# Clocks_Freq_Synth_board.net
KiCad netlist of a schematic drawn in EAGLE
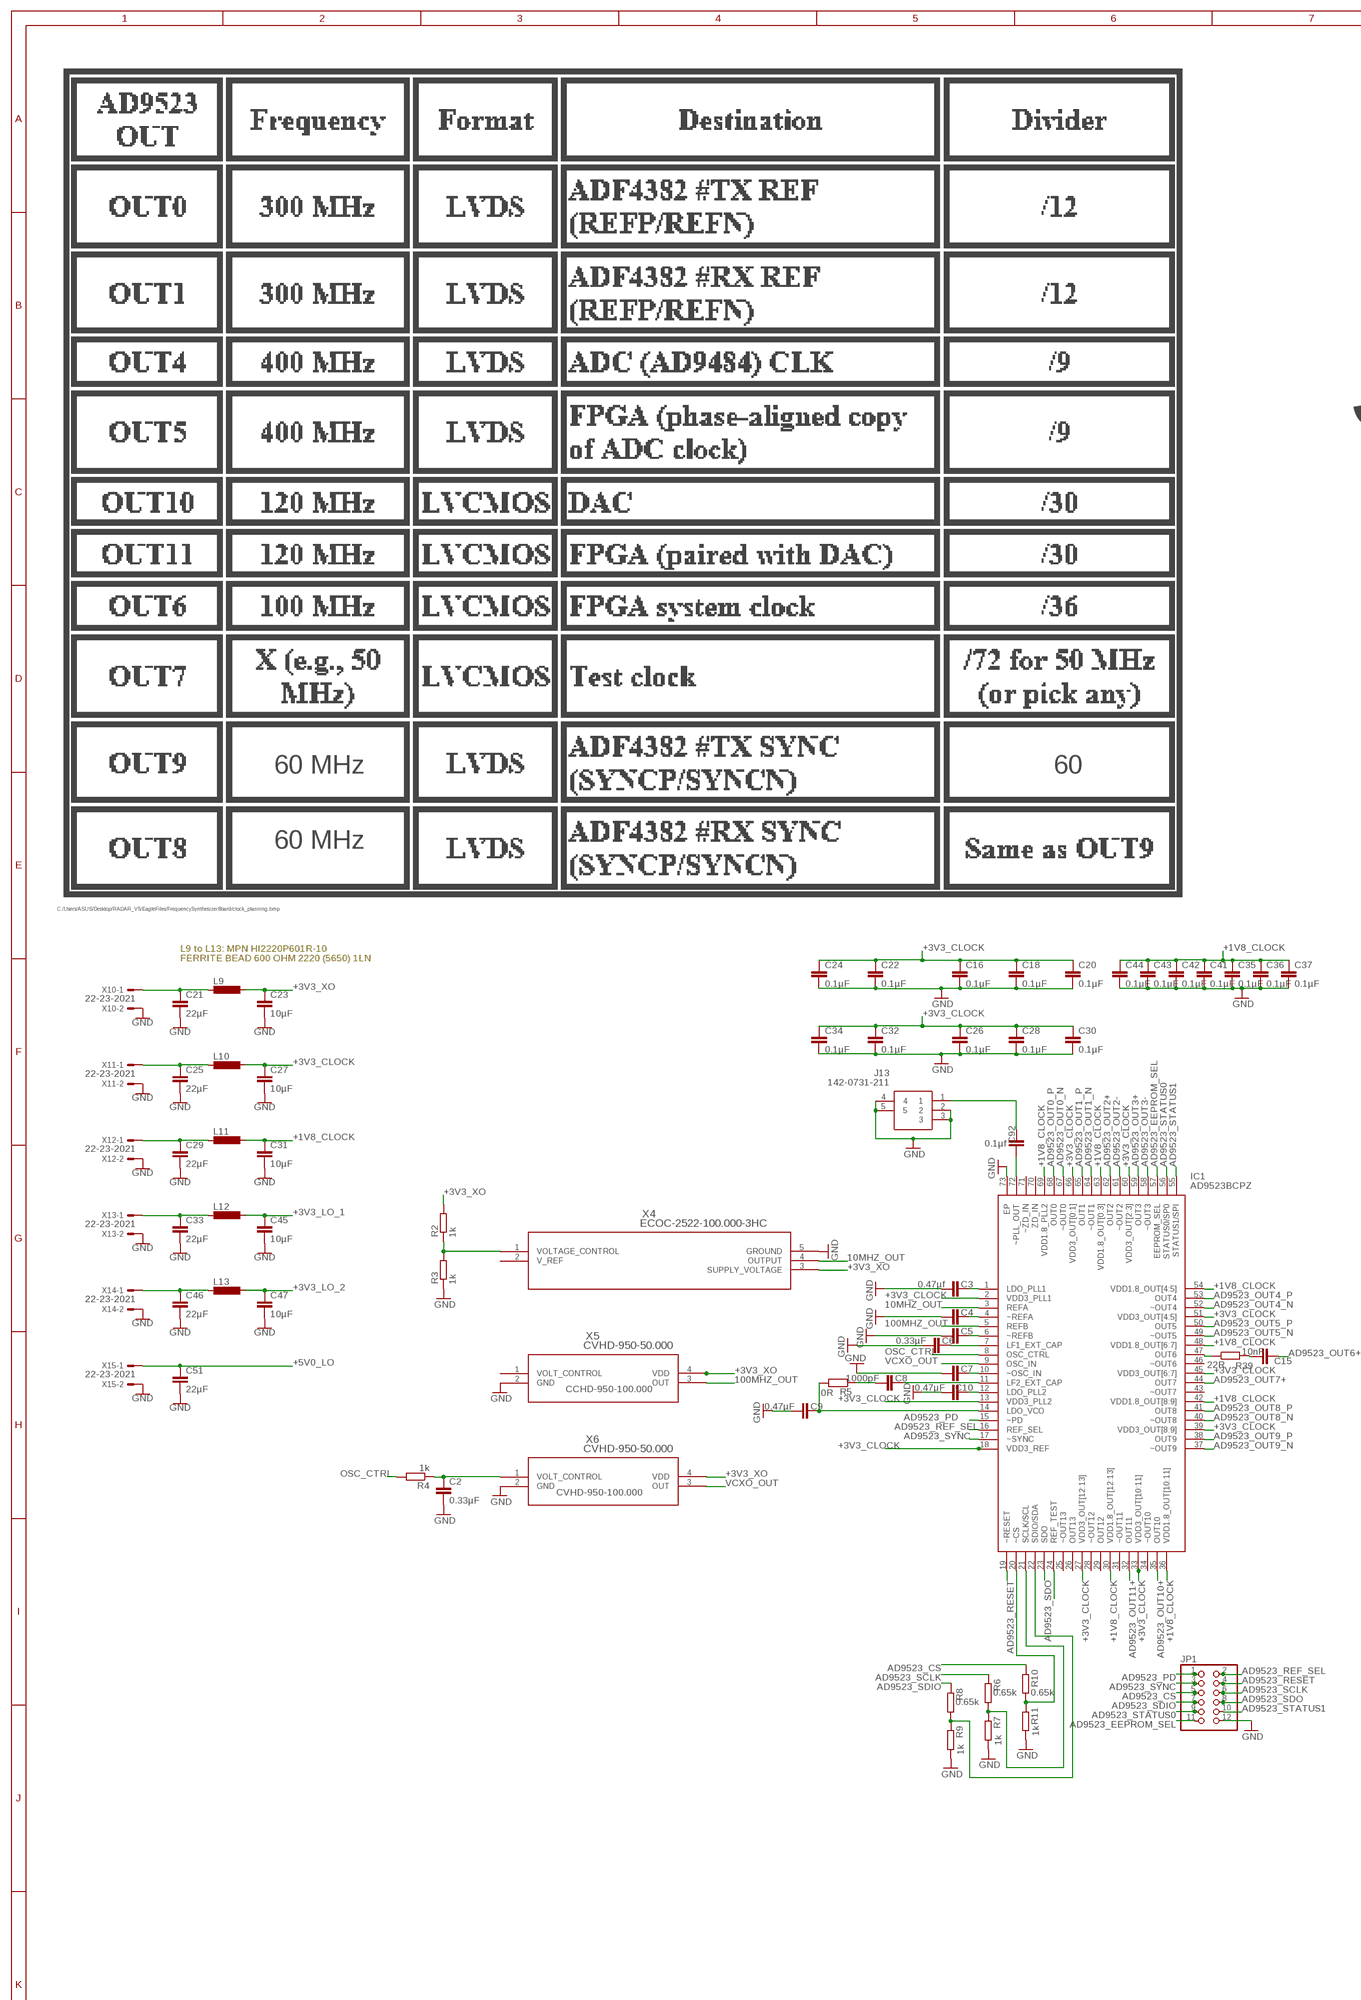
[diagram p0: schematic, sheet 1, part 1 of 3]
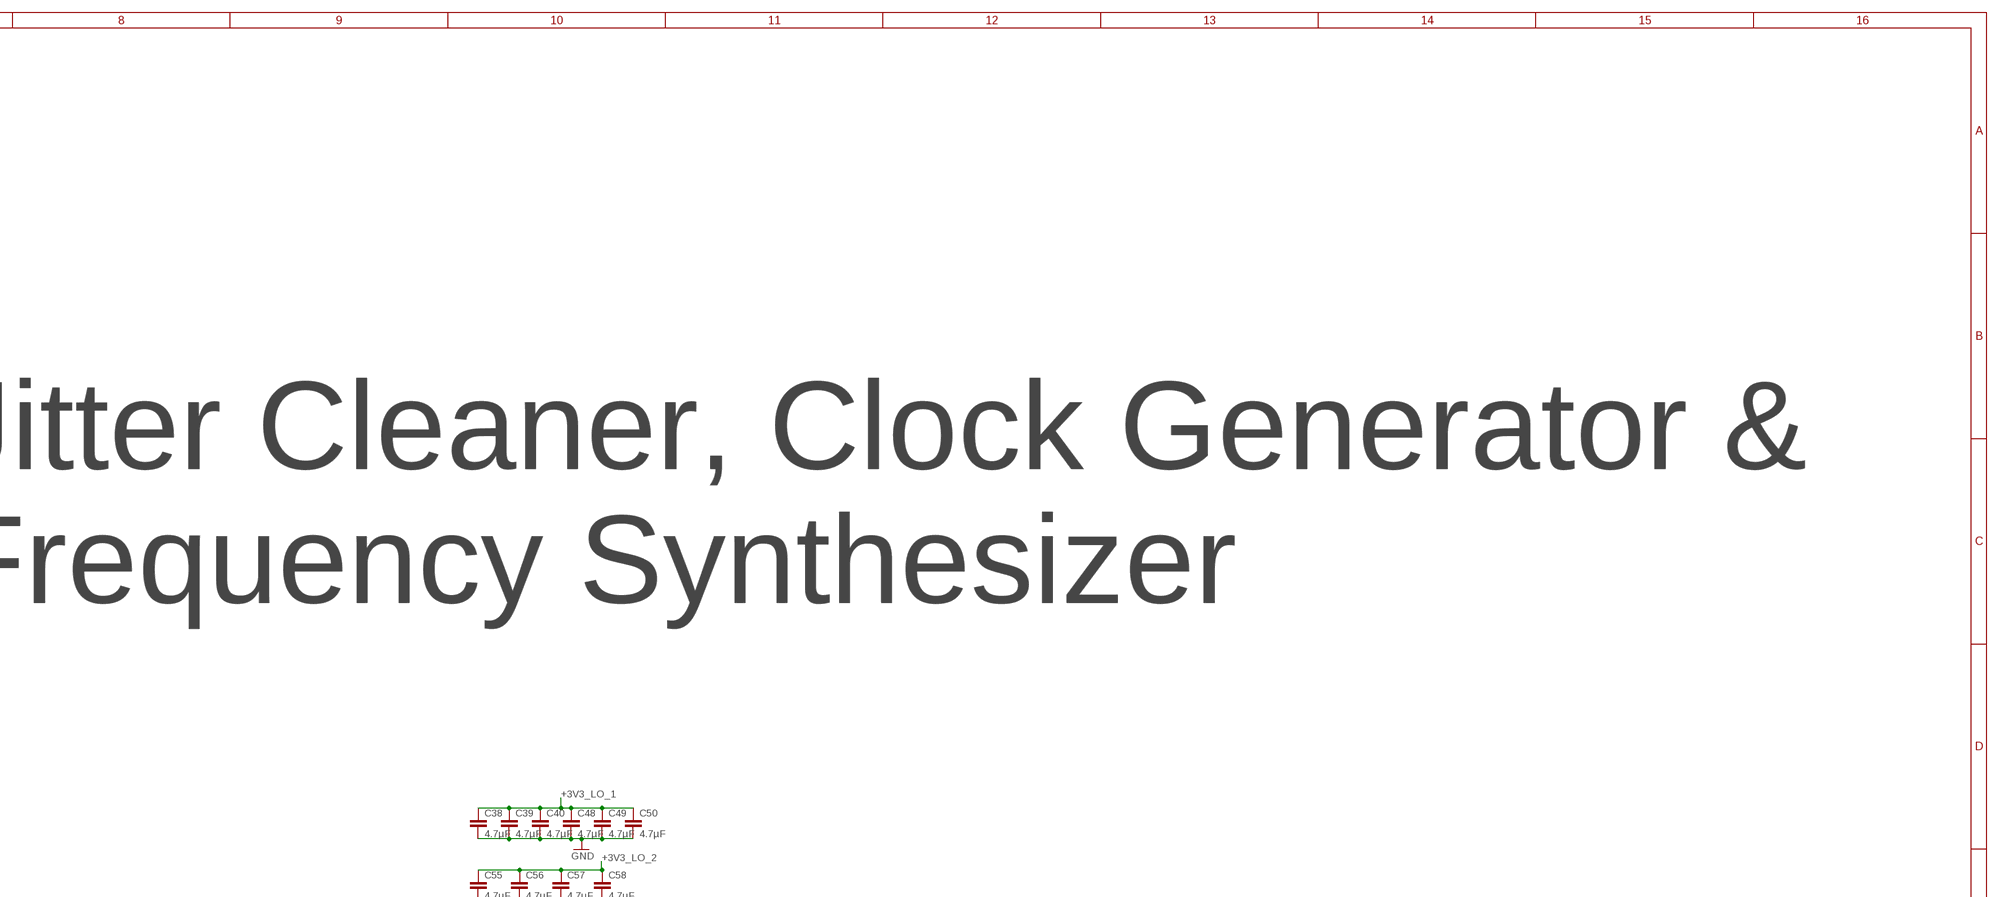
[diagram p1: schematic, sheet 1, part 2 of 3]
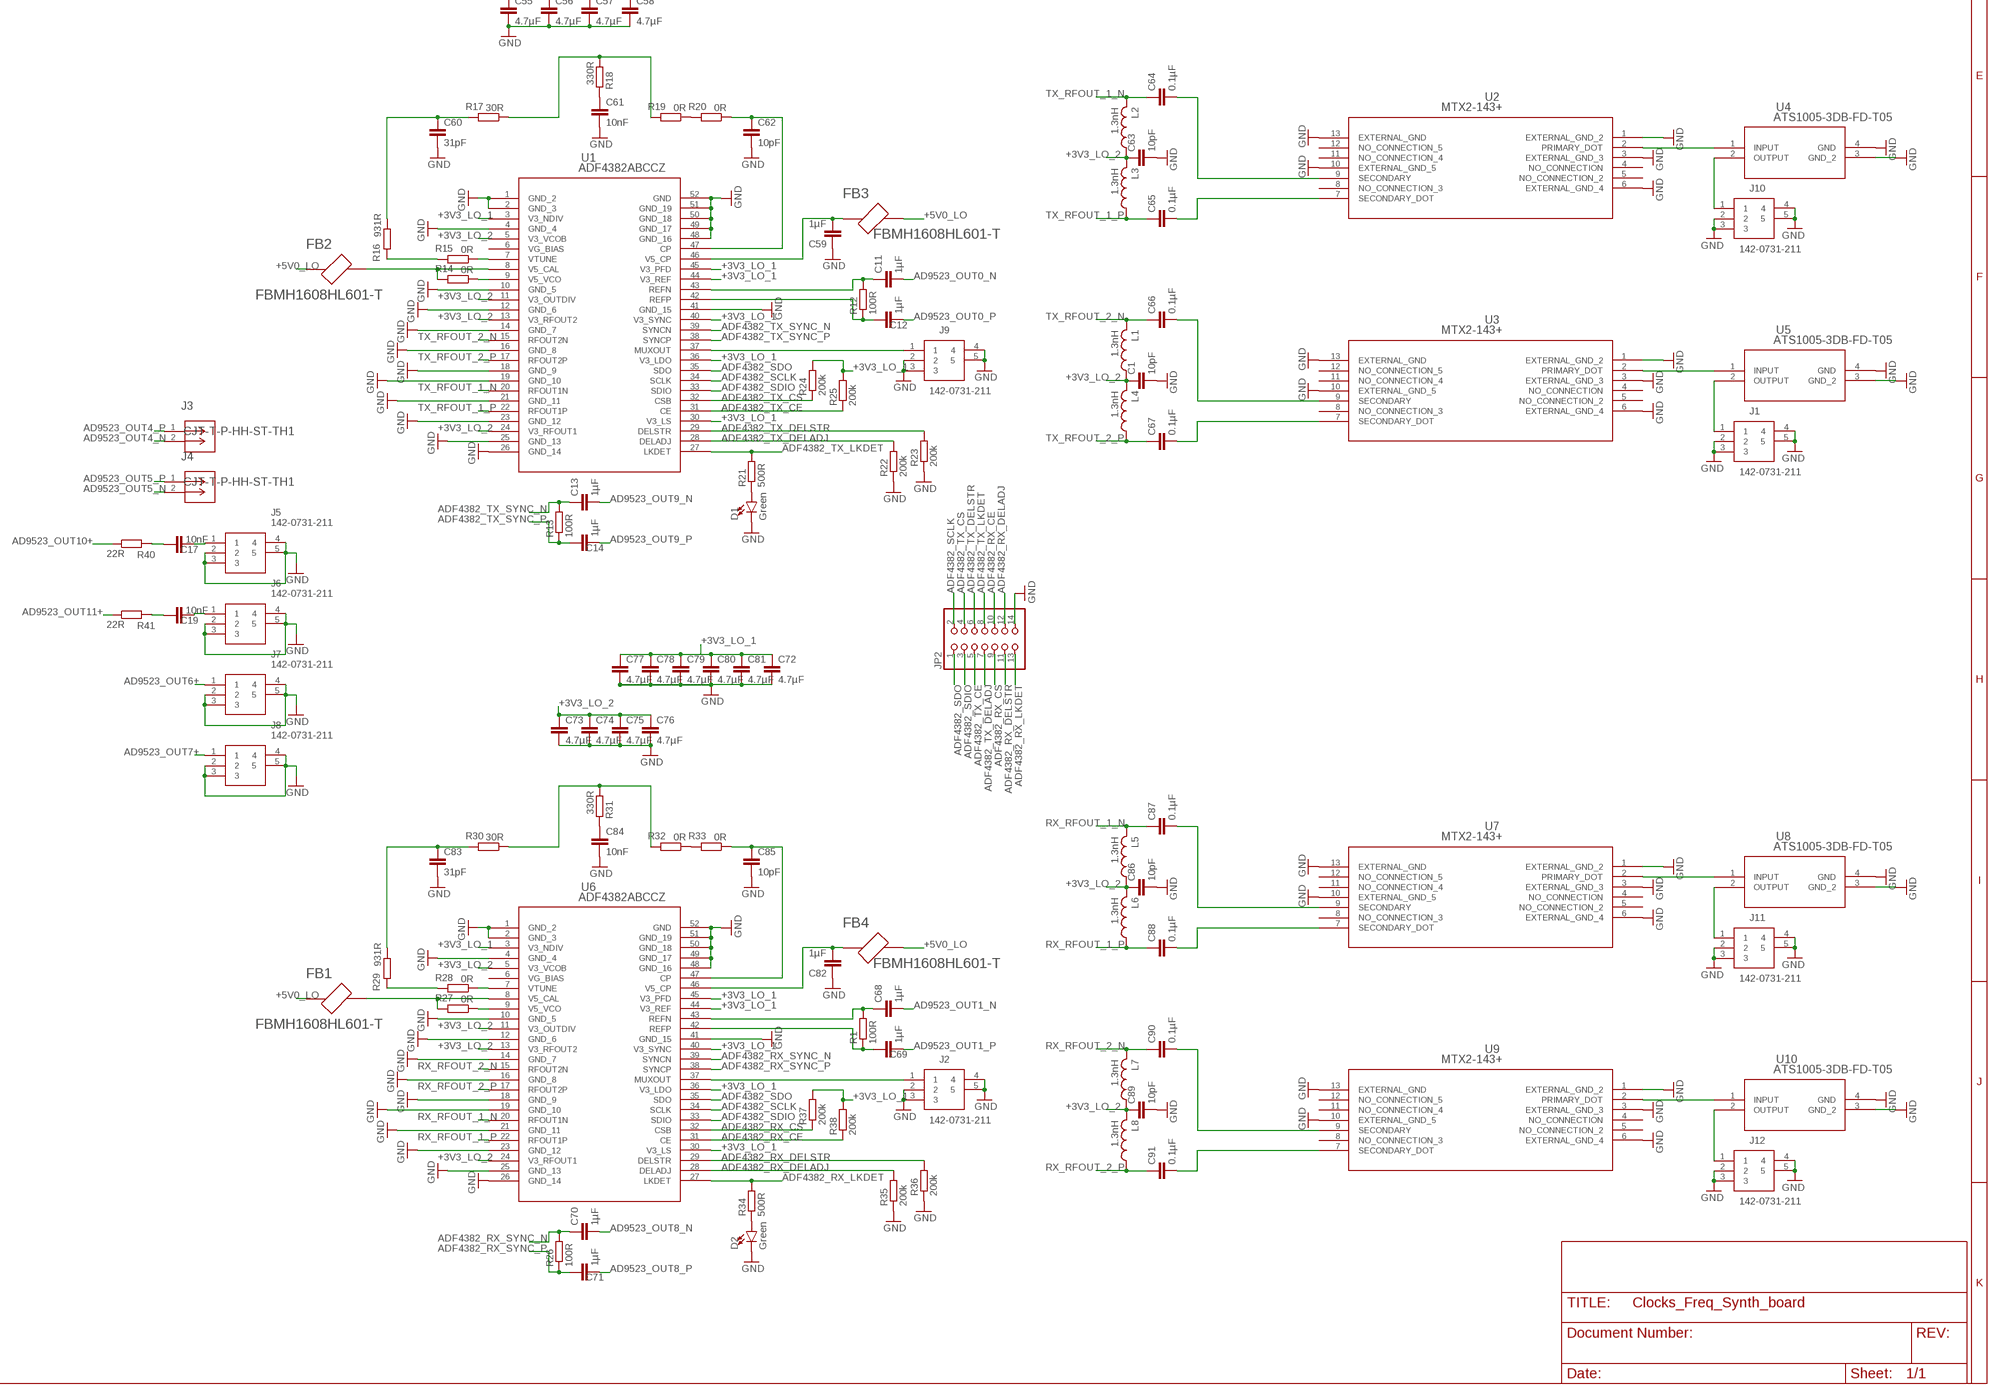
[diagram p2: schematic, sheet 1, part 3 of 3]

(export (version "E")
  (design (tool "Eeschema 10.0.6"))
  (components
    (comp (ref "C1")
      (value "10pF")
      (footprint "eagle-import:C0201")
      (libsource (lib "eagle-import") (part "C-EUC0201"))
    )
    (comp (ref "C2")
      (value "0.33µF")
      (footprint "eagle-import:C0201")
      (libsource (lib "eagle-import") (part "C-EUC0201"))
    )
    (comp (ref "C3")
      (value "0.47µf")
      (footprint "eagle-import:C0201")
      (libsource (lib "eagle-import") (part "C-EUC0201"))
    )
    (comp (ref "C4")
      (value "C-EUC0201")
      (footprint "eagle-import:C0201")
      (libsource (lib "eagle-import") (part "C-EUC0201"))
    )
    (comp (ref "C5")
      (value "C-EUC0201")
      (footprint "eagle-import:C0201")
      (libsource (lib "eagle-import") (part "C-EUC0201"))
    )
    (comp (ref "C6")
      (value "0.33µF")
      (footprint "eagle-import:C0201")
      (libsource (lib "eagle-import") (part "C-EUC0201"))
    )
    (comp (ref "C7")
      (value "C-EUC0201")
      (footprint "eagle-import:C0201")
      (libsource (lib "eagle-import") (part "C-EUC0201"))
    )
    (comp (ref "C8")
      (value "1000pF")
      (footprint "eagle-import:C0201")
      (libsource (lib "eagle-import") (part "C-EUC0201"))
    )
    (comp (ref "C9")
      (value "0.47µF")
      (footprint "eagle-import:C0201")
      (libsource (lib "eagle-import") (part "C-EUC0201"))
    )
    (comp (ref "C10")
      (value "0.47µF")
      (footprint "eagle-import:C0201")
      (libsource (lib "eagle-import") (part "C-EUC0201"))
    )
    (comp (ref "C11")
      (value "1µF")
      (footprint "eagle-import:C0201")
      (libsource (lib "eagle-import") (part "C-EUC0201"))
    )
    (comp (ref "C12")
      (value "1µF")
      (footprint "eagle-import:C0201")
      (libsource (lib "eagle-import") (part "C-EUC0201"))
    )
    (comp (ref "C13")
      (value "1µF")
      (footprint "eagle-import:C0201")
      (libsource (lib "eagle-import") (part "C-EUC0201"))
    )
    (comp (ref "C14")
      (value "1µF")
      (footprint "eagle-import:C0201")
      (libsource (lib "eagle-import") (part "C-EUC0201"))
    )
    (comp (ref "C15")
      (value "10nF")
      (footprint "eagle-import:C0402")
      (libsource (lib "eagle-import") (part "C-EUC0402"))
    )
    (comp (ref "C16")
      (value "0.1µF")
      (footprint "eagle-import:C0201")
      (libsource (lib "eagle-import") (part "C-EUC0201"))
    )
    (comp (ref "C17")
      (value "10nF")
      (footprint "eagle-import:C0402")
      (libsource (lib "eagle-import") (part "C-EUC0402"))
    )
    (comp (ref "C18")
      (value "0.1µF")
      (footprint "eagle-import:C0201")
      (libsource (lib "eagle-import") (part "C-EUC0201"))
    )
    (comp (ref "C19")
      (value "10nF")
      (footprint "eagle-import:C0402")
      (libsource (lib "eagle-import") (part "C-EUC0402"))
    )
    (comp (ref "C20")
      (value "0.1µF")
      (footprint "eagle-import:C0201")
      (libsource (lib "eagle-import") (part "C-EUC0201"))
    )
    (comp (ref "C21")
      (value "22µF")
      (footprint "eagle-import:C1210")
      (libsource (lib "eagle-import") (part "C-EUC1210"))
    )
    (comp (ref "C22")
      (value "0.1µF")
      (footprint "eagle-import:C0201")
      (libsource (lib "eagle-import") (part "C-EUC0201"))
    )
    (comp (ref "C23")
      (value "10µF")
      (footprint "eagle-import:C1210")
      (libsource (lib "eagle-import") (part "C-EUC1210"))
    )
    (comp (ref "C24")
      (value "0.1µF")
      (footprint "eagle-import:C0201")
      (libsource (lib "eagle-import") (part "C-EUC0201"))
    )
    (comp (ref "C25")
      (value "22µF")
      (footprint "eagle-import:C1210")
      (libsource (lib "eagle-import") (part "C-EUC1210"))
    )
    (comp (ref "C26")
      (value "0.1µF")
      (footprint "eagle-import:C0201")
      (libsource (lib "eagle-import") (part "C-EUC0201"))
    )
    (comp (ref "C27")
      (value "10µF")
      (footprint "eagle-import:C1210")
      (libsource (lib "eagle-import") (part "C-EUC1210"))
    )
    (comp (ref "C28")
      (value "0.1µF")
      (footprint "eagle-import:C0201")
      (libsource (lib "eagle-import") (part "C-EUC0201"))
    )
    (comp (ref "C29")
      (value "22µF")
      (footprint "eagle-import:C1210")
      (libsource (lib "eagle-import") (part "C-EUC1210"))
    )
    (comp (ref "C30")
      (value "0.1µF")
      (footprint "eagle-import:C0201")
      (libsource (lib "eagle-import") (part "C-EUC0201"))
    )
    (comp (ref "C31")
      (value "10µF")
      (footprint "eagle-import:C1210")
      (libsource (lib "eagle-import") (part "C-EUC1210"))
    )
    (comp (ref "C32")
      (value "0.1µF")
      (footprint "eagle-import:C0201")
      (libsource (lib "eagle-import") (part "C-EUC0201"))
    )
    (comp (ref "C33")
      (value "22µF")
      (footprint "eagle-import:C1210")
      (libsource (lib "eagle-import") (part "C-EUC1210"))
    )
    (comp (ref "C34")
      (value "0.1µF")
      (footprint "eagle-import:C0201")
      (libsource (lib "eagle-import") (part "C-EUC0201"))
    )
    (comp (ref "C35")
      (value "0.1µF")
      (footprint "eagle-import:C0201")
      (libsource (lib "eagle-import") (part "C-EUC0201"))
    )
    (comp (ref "C36")
      (value "0.1µF")
      (footprint "eagle-import:C0201")
      (libsource (lib "eagle-import") (part "C-EUC0201"))
    )
    (comp (ref "C37")
      (value "0.1µF")
      (footprint "eagle-import:C0201")
      (libsource (lib "eagle-import") (part "C-EUC0201"))
    )
    (comp (ref "C38")
      (value "4.7µF")
      (footprint "eagle-import:C0201")
      (libsource (lib "eagle-import") (part "C-EUC0201"))
    )
    (comp (ref "C39")
      (value "4.7µF")
      (footprint "eagle-import:C0201")
      (libsource (lib "eagle-import") (part "C-EUC0201"))
    )
    (comp (ref "C40")
      (value "4.7µF")
      (footprint "eagle-import:C0201")
      (libsource (lib "eagle-import") (part "C-EUC0201"))
    )
    (comp (ref "C41")
      (value "0.1µF")
      (footprint "eagle-import:C0201")
      (libsource (lib "eagle-import") (part "C-EUC0201"))
    )
    (comp (ref "C42")
      (value "0.1µF")
      (footprint "eagle-import:C0201")
      (libsource (lib "eagle-import") (part "C-EUC0201"))
    )
    (comp (ref "C43")
      (value "0.1µF")
      (footprint "eagle-import:C0201")
      (libsource (lib "eagle-import") (part "C-EUC0201"))
    )
    (comp (ref "C44")
      (value "0.1µF")
      (footprint "eagle-import:C0201")
      (libsource (lib "eagle-import") (part "C-EUC0201"))
    )
    (comp (ref "C45")
      (value "10µF")
      (footprint "eagle-import:C1210")
      (libsource (lib "eagle-import") (part "C-EUC1210"))
    )
    (comp (ref "C46")
      (value "22µF")
      (footprint "eagle-import:C1210")
      (libsource (lib "eagle-import") (part "C-EUC1210"))
    )
    (comp (ref "C47")
      (value "10µF")
      (footprint "eagle-import:C1210")
      (libsource (lib "eagle-import") (part "C-EUC1210"))
    )
    (comp (ref "C48")
      (value "4.7µF")
      (footprint "eagle-import:C0201")
      (libsource (lib "eagle-import") (part "C-EUC0201"))
    )
    (comp (ref "C49")
      (value "4.7µF")
      (footprint "eagle-import:C0201")
      (libsource (lib "eagle-import") (part "C-EUC0201"))
    )
    (comp (ref "C50")
      (value "4.7µF")
      (footprint "eagle-import:C0201")
      (libsource (lib "eagle-import") (part "C-EUC0201"))
    )
    (comp (ref "C51")
      (value "22µF")
      (footprint "eagle-import:C1210")
      (libsource (lib "eagle-import") (part "C-EUC1210"))
    )
    (comp (ref "C55")
      (value "4.7µF")
      (footprint "eagle-import:C0201")
      (libsource (lib "eagle-import") (part "C-EUC0201"))
    )
    (comp (ref "C56")
      (value "4.7µF")
      (footprint "eagle-import:C0201")
      (libsource (lib "eagle-import") (part "C-EUC0201"))
    )
    (comp (ref "C57")
      (value "4.7µF")
      (footprint "eagle-import:C0201")
      (libsource (lib "eagle-import") (part "C-EUC0201"))
    )
    (comp (ref "C58")
      (value "4.7µF")
      (footprint "eagle-import:C0201")
      (libsource (lib "eagle-import") (part "C-EUC0201"))
    )
    (comp (ref "C59")
      (value "1µF")
      (footprint "eagle-import:C0201")
      (libsource (lib "eagle-import") (part "C-EUC0201"))
    )
    (comp (ref "C60")
      (value "31pF")
      (footprint "eagle-import:C0201")
      (libsource (lib "eagle-import") (part "C-EUC0201"))
    )
    (comp (ref "C61")
      (value "10nF")
      (footprint "eagle-import:C0201")
      (libsource (lib "eagle-import") (part "C-EUC0201"))
    )
    (comp (ref "C62")
      (value "10pF")
      (footprint "eagle-import:C0201")
      (libsource (lib "eagle-import") (part "C-EUC0201"))
    )
    (comp (ref "C63")
      (value "10pF")
      (footprint "eagle-import:C0201")
      (libsource (lib "eagle-import") (part "C-EUC0201"))
    )
    (comp (ref "C64")
      (value "0.1µF")
      (footprint "eagle-import:C0201")
      (libsource (lib "eagle-import") (part "C-EUC0201"))
    )
    (comp (ref "C65")
      (value "0.1µF")
      (footprint "eagle-import:C0201")
      (libsource (lib "eagle-import") (part "C-EUC0201"))
    )
    (comp (ref "C66")
      (value "0.1µF")
      (footprint "eagle-import:C0201")
      (libsource (lib "eagle-import") (part "C-EUC0201"))
    )
    (comp (ref "C67")
      (value "0.1µF")
      (footprint "eagle-import:C0201")
      (libsource (lib "eagle-import") (part "C-EUC0201"))
    )
    (comp (ref "C68")
      (value "1µF")
      (footprint "eagle-import:C0201")
      (libsource (lib "eagle-import") (part "C-EUC0201"))
    )
    (comp (ref "C69")
      (value "1µF")
      (footprint "eagle-import:C0201")
      (libsource (lib "eagle-import") (part "C-EUC0201"))
    )
    (comp (ref "C70")
      (value "1µF")
      (footprint "eagle-import:C0201")
      (libsource (lib "eagle-import") (part "C-EUC0201"))
    )
    (comp (ref "C71")
      (value "1µF")
      (footprint "eagle-import:C0201")
      (libsource (lib "eagle-import") (part "C-EUC0201"))
    )
    (comp (ref "C72")
      (value "4.7µF")
      (footprint "eagle-import:C0201")
      (libsource (lib "eagle-import") (part "C-EUC0201"))
    )
    (comp (ref "C73")
      (value "4.7µF")
      (footprint "eagle-import:C0201")
      (libsource (lib "eagle-import") (part "C-EUC0201"))
    )
    (comp (ref "C74")
      (value "4.7µF")
      (footprint "eagle-import:C0201")
      (libsource (lib "eagle-import") (part "C-EUC0201"))
    )
    (comp (ref "C75")
      (value "4.7µF")
      (footprint "eagle-import:C0201")
      (libsource (lib "eagle-import") (part "C-EUC0201"))
    )
    (comp (ref "C76")
      (value "4.7µF")
      (footprint "eagle-import:C0201")
      (libsource (lib "eagle-import") (part "C-EUC0201"))
    )
    (comp (ref "C77")
      (value "4.7µF")
      (footprint "eagle-import:C0201")
      (libsource (lib "eagle-import") (part "C-EUC0201"))
    )
    (comp (ref "C78")
      (value "4.7µF")
      (footprint "eagle-import:C0201")
      (libsource (lib "eagle-import") (part "C-EUC0201"))
    )
    (comp (ref "C79")
      (value "4.7µF")
      (footprint "eagle-import:C0201")
      (libsource (lib "eagle-import") (part "C-EUC0201"))
    )
    (comp (ref "C80")
      (value "4.7µF")
      (footprint "eagle-import:C0201")
      (libsource (lib "eagle-import") (part "C-EUC0201"))
    )
    (comp (ref "C81")
      (value "4.7µF")
      (footprint "eagle-import:C0201")
      (libsource (lib "eagle-import") (part "C-EUC0201"))
    )
    (comp (ref "C82")
      (value "1µF")
      (footprint "eagle-import:C0201")
      (libsource (lib "eagle-import") (part "C-EUC0201"))
    )
    (comp (ref "C83")
      (value "31pF")
      (footprint "eagle-import:C0201")
      (libsource (lib "eagle-import") (part "C-EUC0201"))
    )
    (comp (ref "C84")
      (value "10nF")
      (footprint "eagle-import:C0201")
      (libsource (lib "eagle-import") (part "C-EUC0201"))
    )
    (comp (ref "C85")
      (value "10pF")
      (footprint "eagle-import:C0201")
      (libsource (lib "eagle-import") (part "C-EUC0201"))
    )
    (comp (ref "C86")
      (value "10pF")
      (footprint "eagle-import:C0201")
      (libsource (lib "eagle-import") (part "C-EUC0201"))
    )
    (comp (ref "C87")
      (value "0.1µF")
      (footprint "eagle-import:C0201")
      (libsource (lib "eagle-import") (part "C-EUC0201"))
    )
    (comp (ref "C88")
      (value "0.1µF")
      (footprint "eagle-import:C0201")
      (libsource (lib "eagle-import") (part "C-EUC0201"))
    )
    (comp (ref "C89")
      (value "10pF")
      (footprint "eagle-import:C0201")
      (libsource (lib "eagle-import") (part "C-EUC0201"))
    )
    (comp (ref "C90")
      (value "0.1µF")
      (footprint "eagle-import:C0201")
      (libsource (lib "eagle-import") (part "C-EUC0201"))
    )
    (comp (ref "C91")
      (value "0.1µF")
      (footprint "eagle-import:C0201")
      (libsource (lib "eagle-import") (part "C-EUC0201"))
    )
    (comp (ref "C92")
      (value "0.1µf")
      (footprint "eagle-import:C0201")
      (libsource (lib "eagle-import") (part "C-EUC0201"))
    )
    (comp (ref "D1")
      (value "Green")
      (footprint "eagle-import:LED-0603")
      (libsource (lib "eagle-import") (part "LED-GREEN-0603-WE"))
    )
    (comp (ref "D2")
      (value "Green")
      (footprint "eagle-import:LED-0603")
      (libsource (lib "eagle-import") (part "LED-GREEN-0603-WE"))
    )
    (comp (ref "FB1")
      (value "FBMH1608HL601-T")
      (footprint "eagle-import:BEADC1608X90N")
      (libsource (lib "eagle-import") (part "FBMH1608HL601-T"))
    )
    (comp (ref "FB2")
      (value "FBMH1608HL601-T")
      (footprint "eagle-import:BEADC1608X90N")
      (libsource (lib "eagle-import") (part "FBMH1608HL601-T"))
    )
    (comp (ref "FB3")
      (value "FBMH1608HL601-T")
      (footprint "eagle-import:BEADC1608X90N")
      (libsource (lib "eagle-import") (part "FBMH1608HL601-T"))
    )
    (comp (ref "FB4")
      (value "FBMH1608HL601-T")
      (footprint "eagle-import:BEADC1608X90N")
      (libsource (lib "eagle-import") (part "FBMH1608HL601-T"))
    )
    (comp (ref "IC1")
      (value "AD9523BCPZ")
      (footprint "eagle-import:QFN50P1000X1000X100-73N")
      (fields (field (name "MOUSER_PART_NUMBER") "584-AD9523BCPZ"))
      (libsource (lib "eagle-import") (part "AD9523BCPZ"))
    )
    (comp (ref "J1")
      (value "142-0731-211")
      (footprint "eagle-import:1420731211")
      (fields (field (name "MOUSER_PART_NUMBER") "530-142-0731-211"))
      (libsource (lib "eagle-import") (part "142-0731-211"))
    )
    (comp (ref "J2")
      (value "142-0731-211")
      (footprint "eagle-import:1420731211")
      (fields (field (name "MOUSER_PART_NUMBER") "530-142-0731-211"))
      (libsource (lib "eagle-import") (part "142-0731-211"))
    )
    (comp (ref "J3")
      (value "CJT-T-P-HH-ST-TH1")
      (footprint "eagle-import:CONN_CJT-T-P-XX-ST-TH1_SAI")
      (fields (field (name "COPYRIGHT") "Copyright (C) 2025 Ultra Librarian. All rights reserved."))
      (libsource (lib "eagle-import") (part "CJT-T-P-HH-ST-TH1"))
    )
    (comp (ref "J4")
      (value "CJT-T-P-HH-ST-TH1")
      (footprint "eagle-import:CONN_CJT-T-P-XX-ST-TH1_SAI")
      (fields (field (name "COPYRIGHT") "Copyright (C) 2025 Ultra Librarian. All rights reserved."))
      (libsource (lib "eagle-import") (part "CJT-T-P-HH-ST-TH1"))
    )
    (comp (ref "J5")
      (value "142-0731-211")
      (footprint "eagle-import:1420731211")
      (fields (field (name "MOUSER_PART_NUMBER") "530-142-0731-211"))
      (libsource (lib "eagle-import") (part "142-0731-211"))
    )
    (comp (ref "J6")
      (value "142-0731-211")
      (footprint "eagle-import:1420731211")
      (fields (field (name "MOUSER_PART_NUMBER") "530-142-0731-211"))
      (libsource (lib "eagle-import") (part "142-0731-211"))
    )
    (comp (ref "J7")
      (value "142-0731-211")
      (footprint "eagle-import:1420731211")
      (fields (field (name "MOUSER_PART_NUMBER") "530-142-0731-211"))
      (libsource (lib "eagle-import") (part "142-0731-211"))
    )
    (comp (ref "J8")
      (value "142-0731-211")
      (footprint "eagle-import:1420731211")
      (fields (field (name "MOUSER_PART_NUMBER") "530-142-0731-211"))
      (libsource (lib "eagle-import") (part "142-0731-211"))
    )
    (comp (ref "J9")
      (value "142-0731-211")
      (footprint "eagle-import:1420731211")
      (fields (field (name "MOUSER_PART_NUMBER") "530-142-0731-211"))
      (libsource (lib "eagle-import") (part "142-0731-211"))
    )
    (comp (ref "J10")
      (value "142-0731-211")
      (footprint "eagle-import:1420731211")
      (fields (field (name "MOUSER_PART_NUMBER") "530-142-0731-211"))
      (libsource (lib "eagle-import") (part "142-0731-211"))
    )
    (comp (ref "J11")
      (value "142-0731-211")
      (footprint "eagle-import:1420731211")
      (fields (field (name "MOUSER_PART_NUMBER") "530-142-0731-211"))
      (libsource (lib "eagle-import") (part "142-0731-211"))
    )
    (comp (ref "J12")
      (value "142-0731-211")
      (footprint "eagle-import:1420731211")
      (fields (field (name "MOUSER_PART_NUMBER") "530-142-0731-211"))
      (libsource (lib "eagle-import") (part "142-0731-211"))
    )
    (comp (ref "J13")
      (value "142-0731-211")
      (footprint "eagle-import:1420731211")
      (fields (field (name "MOUSER_PART_NUMBER") "530-142-0731-211"))
      (libsource (lib "eagle-import") (part "142-0731-211"))
    )
    (comp (ref "JP1")
      (value "PINHD-2X6")
      (footprint "eagle-import:2X06")
      (libsource (lib "eagle-import") (part "PINHD-2X6"))
    )
    (comp (ref "JP2")
      (value "PINHD-2X7")
      (footprint "eagle-import:2X07")
      (libsource (lib "eagle-import") (part "PINHD-2X7"))
    )
    (comp (ref "L1")
      (value "1.3nH")
      (footprint "eagle-import:L0201")
      (libsource (lib "eagle-import") (part "L-USL0201"))
    )
    (comp (ref "L2")
      (value "1.3nH")
      (footprint "eagle-import:L0201")
      (libsource (lib "eagle-import") (part "L-USL0201"))
    )
    (comp (ref "L3")
      (value "1.3nH")
      (footprint "eagle-import:L0201")
      (libsource (lib "eagle-import") (part "L-USL0201"))
    )
    (comp (ref "L4")
      (value "1.3nH")
      (footprint "eagle-import:L0201")
      (libsource (lib "eagle-import") (part "L-USL0201"))
    )
    (comp (ref "L5")
      (value "1.3nH")
      (footprint "eagle-import:L0201")
      (libsource (lib "eagle-import") (part "L-USL0201"))
    )
    (comp (ref "L6")
      (value "1.3nH")
      (footprint "eagle-import:L0201")
      (libsource (lib "eagle-import") (part "L-USL0201"))
    )
    (comp (ref "L7")
      (value "1.3nH")
      (footprint "eagle-import:L0201")
      (libsource (lib "eagle-import") (part "L-USL0201"))
    )
    (comp (ref "L8")
      (value "1.3nH")
      (footprint "eagle-import:L0201")
      (libsource (lib "eagle-import") (part "L-USL0201"))
    )
    (comp (ref "L9")
      (value "L-EUL5650M")
      (footprint "eagle-import:L5650M")
      (libsource (lib "eagle-import") (part "L-EUL5650M"))
    )
    (comp (ref "L10")
      (value "L-EUL5650M")
      (footprint "eagle-import:L5650M")
      (libsource (lib "eagle-import") (part "L-EUL5650M"))
    )
    (comp (ref "L11")
      (value "L-EUL5650M")
      (footprint "eagle-import:L5650M")
      (libsource (lib "eagle-import") (part "L-EUL5650M"))
    )
    (comp (ref "L12")
      (value "L-EUL5650M")
      (footprint "eagle-import:L5650M")
      (libsource (lib "eagle-import") (part "L-EUL5650M"))
    )
    (comp (ref "L13")
      (value "L-EUL5650M")
      (footprint "eagle-import:L5650M")
      (libsource (lib "eagle-import") (part "L-EUL5650M"))
    )
    (comp (ref "R1")
      (value "100R")
      (footprint "eagle-import:R0201")
      (libsource (lib "eagle-import") (part "R-EU_R0201"))
    )
    (comp (ref "R2")
      (value "1k")
      (footprint "eagle-import:R0201")
      (libsource (lib "eagle-import") (part "R-EU_R0201"))
    )
    (comp (ref "R3")
      (value "1k")
      (footprint "eagle-import:R0201")
      (libsource (lib "eagle-import") (part "R-EU_R0201"))
    )
    (comp (ref "R4")
      (value "1k")
      (footprint "eagle-import:R0201")
      (libsource (lib "eagle-import") (part "R-EU_R0201"))
    )
    (comp (ref "R5")
      (value "0R")
      (footprint "eagle-import:R0201")
      (libsource (lib "eagle-import") (part "R-EU_R0201"))
    )
    (comp (ref "R6")
      (value "0.65k")
      (footprint "eagle-import:R0201")
      (libsource (lib "eagle-import") (part "R-EU_R0201"))
    )
    (comp (ref "R7")
      (value "1k")
      (footprint "eagle-import:R0201")
      (libsource (lib "eagle-import") (part "R-EU_R0201"))
    )
    (comp (ref "R8")
      (value "0.65k")
      (footprint "eagle-import:R0201")
      (libsource (lib "eagle-import") (part "R-EU_R0201"))
    )
    (comp (ref "R9")
      (value "1k")
      (footprint "eagle-import:R0201")
      (libsource (lib "eagle-import") (part "R-EU_R0201"))
    )
    (comp (ref "R10")
      (value "0.65k")
      (footprint "eagle-import:R0201")
      (libsource (lib "eagle-import") (part "R-EU_R0201"))
    )
    (comp (ref "R11")
      (value "1k")
      (footprint "eagle-import:R0201")
      (libsource (lib "eagle-import") (part "R-EU_R0201"))
    )
    (comp (ref "R12")
      (value "100R")
      (footprint "eagle-import:R0201")
      (libsource (lib "eagle-import") (part "R-EU_R0201"))
    )
    (comp (ref "R13")
      (value "100R")
      (footprint "eagle-import:R0201")
      (libsource (lib "eagle-import") (part "R-EU_R0201"))
    )
    (comp (ref "R14")
      (value "0R")
      (footprint "eagle-import:R0201")
      (libsource (lib "eagle-import") (part "R-EU_R0201"))
    )
    (comp (ref "R15")
      (value "0R")
      (footprint "eagle-import:R0201")
      (libsource (lib "eagle-import") (part "R-EU_R0201"))
    )
    (comp (ref "R16")
      (value "931R")
      (footprint "eagle-import:R0201")
      (libsource (lib "eagle-import") (part "R-EU_R0201"))
    )
    (comp (ref "R17")
      (value "30R")
      (footprint "eagle-import:R0201")
      (libsource (lib "eagle-import") (part "R-EU_R0201"))
    )
    (comp (ref "R18")
      (value "330R")
      (footprint "eagle-import:R0201")
      (libsource (lib "eagle-import") (part "R-EU_R0201"))
    )
    (comp (ref "R19")
      (value "0R")
      (footprint "eagle-import:R0201")
      (libsource (lib "eagle-import") (part "R-EU_R0201"))
    )
    (comp (ref "R20")
      (value "0R")
      (footprint "eagle-import:R0201")
      (libsource (lib "eagle-import") (part "R-EU_R0201"))
    )
    (comp (ref "R21")
      (value "500R")
      (footprint "eagle-import:R0201")
      (libsource (lib "eagle-import") (part "R-EU_R0201"))
    )
    (comp (ref "R22")
      (value "200k")
      (footprint "eagle-import:R0201")
      (libsource (lib "eagle-import") (part "R-EU_R0201"))
    )
    (comp (ref "R23")
      (value "200k")
      (footprint "eagle-import:R0201")
      (libsource (lib "eagle-import") (part "R-EU_R0201"))
    )
    (comp (ref "R24")
      (value "200k")
      (footprint "eagle-import:R0201")
      (libsource (lib "eagle-import") (part "R-EU_R0201"))
    )
    (comp (ref "R25")
      (value "200k")
      (footprint "eagle-import:R0201")
      (libsource (lib "eagle-import") (part "R-EU_R0201"))
    )
    (comp (ref "R26")
      (value "100R")
      (footprint "eagle-import:R0201")
      (libsource (lib "eagle-import") (part "R-EU_R0201"))
    )
    (comp (ref "R27")
      (value "0R")
      (footprint "eagle-import:R0201")
      (libsource (lib "eagle-import") (part "R-EU_R0201"))
    )
    (comp (ref "R28")
      (value "0R")
      (footprint "eagle-import:R0201")
      (libsource (lib "eagle-import") (part "R-EU_R0201"))
    )
    (comp (ref "R29")
      (value "931R")
      (footprint "eagle-import:R0201")
      (libsource (lib "eagle-import") (part "R-EU_R0201"))
    )
    (comp (ref "R30")
      (value "30R")
      (footprint "eagle-import:R0201")
      (libsource (lib "eagle-import") (part "R-EU_R0201"))
    )
    (comp (ref "R31")
      (value "330R")
      (footprint "eagle-import:R0201")
      (libsource (lib "eagle-import") (part "R-EU_R0201"))
    )
    (comp (ref "R32")
      (value "0R")
      (footprint "eagle-import:R0201")
      (libsource (lib "eagle-import") (part "R-EU_R0201"))
    )
    (comp (ref "R33")
      (value "0R")
      (footprint "eagle-import:R0201")
      (libsource (lib "eagle-import") (part "R-EU_R0201"))
    )
    (comp (ref "R34")
      (value "500R")
      (footprint "eagle-import:R0201")
      (libsource (lib "eagle-import") (part "R-EU_R0201"))
    )
    (comp (ref "R35")
      (value "200k")
      (footprint "eagle-import:R0201")
      (libsource (lib "eagle-import") (part "R-EU_R0201"))
    )
    (comp (ref "R36")
      (value "200k")
      (footprint "eagle-import:R0201")
      (libsource (lib "eagle-import") (part "R-EU_R0201"))
    )
    (comp (ref "R37")
      (value "200k")
      (footprint "eagle-import:R0201")
      (libsource (lib "eagle-import") (part "R-EU_R0201"))
    )
    (comp (ref "R38")
      (value "200k")
      (footprint "eagle-import:R0201")
      (libsource (lib "eagle-import") (part "R-EU_R0201"))
    )
    (comp (ref "R39")
      (value "22R")
      (footprint "eagle-import:R0201")
      (libsource (lib "eagle-import") (part "R-EU_R0201"))
    )
    (comp (ref "R40")
      (value "22R")
      (footprint "eagle-import:R0201")
      (libsource (lib "eagle-import") (part "R-EU_R0201"))
    )
    (comp (ref "R41")
      (value "22R")
      (footprint "eagle-import:R0201")
      (libsource (lib "eagle-import") (part "R-EU_R0201"))
    )
    (comp (ref "U1")
      (value "ADF4382ABCCZ")
      (footprint "eagle-import:CC-48-10_ADI")
      (fields (field (name "COPYRIGHT") "Copyright (C) 2024 Ultra Librarian. All rights reserved."))
      (libsource (lib "eagle-import") (part "ADF4382ABCCZ"))
    )
    (comp (ref "U2")
      (value "MTX2-143+")
      (footprint "eagle-import:DQ1225_MNC")
      (fields (field (name "COPYRIGHT") "Copyright (C) 2024 Ultra Librarian. All rights reserved."))
      (libsource (lib "eagle-import") (part "MTX2-143+"))
    )
    (comp (ref "U3")
      (value "MTX2-143+")
      (footprint "eagle-import:DQ1225_MNC")
      (fields (field (name "COPYRIGHT") "Copyright (C) 2024 Ultra Librarian. All rights reserved."))
      (libsource (lib "eagle-import") (part "MTX2-143+"))
    )
    (comp (ref "U4")
      (value "ATS1005-3DB-FD-T05")
      (footprint "eagle-import:SMT_DB-FD-T05_SUS")
      (fields (field (name "COPYRIGHT") "Copyright (C) 2025 Ultra Librarian. All rights reserved."))
      (libsource (lib "eagle-import") (part "ATS1005-3DB-FD-T05"))
    )
    (comp (ref "U5")
      (value "ATS1005-3DB-FD-T05")
      (footprint "eagle-import:SMT_DB-FD-T05_SUS")
      (fields (field (name "COPYRIGHT") "Copyright (C) 2025 Ultra Librarian. All rights reserved."))
      (libsource (lib "eagle-import") (part "ATS1005-3DB-FD-T05"))
    )
    (comp (ref "U6")
      (value "ADF4382ABCCZ")
      (footprint "eagle-import:CC-48-10_ADI")
      (fields (field (name "COPYRIGHT") "Copyright (C) 2024 Ultra Librarian. All rights reserved."))
      (libsource (lib "eagle-import") (part "ADF4382ABCCZ"))
    )
    (comp (ref "U7")
      (value "MTX2-143+")
      (footprint "eagle-import:DQ1225_MNC")
      (fields (field (name "COPYRIGHT") "Copyright (C) 2024 Ultra Librarian. All rights reserved."))
      (libsource (lib "eagle-import") (part "MTX2-143+"))
    )
    (comp (ref "U8")
      (value "ATS1005-3DB-FD-T05")
      (footprint "eagle-import:SMT_DB-FD-T05_SUS")
      (fields (field (name "COPYRIGHT") "Copyright (C) 2025 Ultra Librarian. All rights reserved."))
      (libsource (lib "eagle-import") (part "ATS1005-3DB-FD-T05"))
    )
    (comp (ref "U9")
      (value "MTX2-143+")
      (footprint "eagle-import:DQ1225_MNC")
      (fields (field (name "COPYRIGHT") "Copyright (C) 2024 Ultra Librarian. All rights reserved."))
      (libsource (lib "eagle-import") (part "MTX2-143+"))
    )
    (comp (ref "U10")
      (value "ATS1005-3DB-FD-T05")
      (footprint "eagle-import:SMT_DB-FD-T05_SUS")
      (fields (field (name "COPYRIGHT") "Copyright (C) 2025 Ultra Librarian. All rights reserved."))
      (libsource (lib "eagle-import") (part "ATS1005-3DB-FD-T05"))
    )
    (comp (ref "X4")
      (value "ECOC-2522-100.000-3HC")
      (footprint "eagle-import:SMD5_ECOC-2522_25P4X22_ECS")
      (fields (field (name "COPYRIGHT") "Copyright (C) 2025 Ultra Librarian. All rights reserved."))
      (libsource (lib "eagle-import") (part "ECOC-2522-100.000-3HC"))
    )
    (comp (ref "X5")
      (value "CVHD-950-50.000")
      (footprint "eagle-import:SMD4_CVHD-950_CRX")
      (fields (field (name "COPYRIGHT") "Copyright (C) 2025 Ultra Librarian. All rights reserved."))
      (libsource (lib "eagle-import") (part "CVHD-950-50.000"))
    )
    (comp (ref "X6")
      (value "CVHD-950-50.000")
      (footprint "eagle-import:SMD4_CVHD-950_CRX")
      (fields (field (name "COPYRIGHT") "Copyright (C) 2025 Ultra Librarian. All rights reserved."))
      (libsource (lib "eagle-import") (part "CVHD-950-50.000"))
    )
    (comp (ref "X10")
      (value "22-23-2021")
      (footprint "eagle-import:22-23-2021")
      (fields (field (name "MF") "MOLEX"))
      (libsource (lib "eagle-import") (part "22-23-2021"))
    )
    (comp (ref "X11")
      (value "22-23-2021")
      (footprint "eagle-import:22-23-2021")
      (fields (field (name "MF") "MOLEX"))
      (libsource (lib "eagle-import") (part "22-23-2021"))
    )
    (comp (ref "X12")
      (value "22-23-2021")
      (footprint "eagle-import:22-23-2021")
      (fields (field (name "MF") "MOLEX"))
      (libsource (lib "eagle-import") (part "22-23-2021"))
    )
    (comp (ref "X13")
      (value "22-23-2021")
      (footprint "eagle-import:22-23-2021")
      (fields (field (name "MF") "MOLEX"))
      (libsource (lib "eagle-import") (part "22-23-2021"))
    )
    (comp (ref "X14")
      (value "22-23-2021")
      (footprint "eagle-import:22-23-2021")
      (fields (field (name "MF") "MOLEX"))
      (libsource (lib "eagle-import") (part "22-23-2021"))
    )
    (comp (ref "X15")
      (value "22-23-2021")
      (footprint "eagle-import:22-23-2021")
      (fields (field (name "MF") "MOLEX"))
      (libsource (lib "eagle-import") (part "22-23-2021"))
    )
  )
  (nets
    (net (code "1") (name "/+1V8_CLOCK") (class "Default")
      (node (ref "C31") (pin "1") (pinfunction "1_1") (pintype "passive"))
      (node (ref "C35") (pin "1") (pinfunction "1_1") (pintype "passive"))
      (node (ref "C36") (pin "1") (pinfunction "1_1") (pintype "passive"))
      (node (ref "C37") (pin "1") (pinfunction "1_1") (pintype "passive"))
      (node (ref "C41") (pin "1") (pinfunction "1_1") (pintype "passive"))
      (node (ref "C42") (pin "1") (pinfunction "1_1") (pintype "passive"))
      (node (ref "C43") (pin "1") (pinfunction "1_1") (pintype "passive"))
      (node (ref "C44") (pin "1") (pinfunction "1_1") (pintype "passive"))
      (node (ref "IC1") (pin "30") (pinfunction "VDD1.8_OUT[12:13]_30") (pintype "bidirectional"))
      (node (ref "IC1") (pin "36") (pinfunction "VDD1.8_OUT[10:11]_36") (pintype "bidirectional"))
      (node (ref "IC1") (pin "42") (pinfunction "VDD1.8_OUT[8:9]_42") (pintype "bidirectional"))
      (node (ref "IC1") (pin "48") (pinfunction "VDD1.8_OUT[6:7]_48") (pintype "bidirectional"))
      (node (ref "IC1") (pin "54") (pinfunction "VDD1.8_OUT[4:5]_54") (pintype "bidirectional"))
      (node (ref "IC1") (pin "63") (pinfunction "VDD1.8_OUT[0:3]_63") (pintype "bidirectional"))
      (node (ref "IC1") (pin "69") (pinfunction "VDD1.8_PLL2_69") (pintype "bidirectional"))
      (node (ref "L11") (pin "1") (pinfunction "1_1") (pintype "passive"))
    )
    (net (code "2") (name "/+3V3_CLOCK") (class "Default")
      (node (ref "C16") (pin "1") (pinfunction "1_1") (pintype "passive"))
      (node (ref "C18") (pin "1") (pinfunction "1_1") (pintype "passive"))
      (node (ref "C20") (pin "1") (pinfunction "1_1") (pintype "passive"))
      (node (ref "C22") (pin "1") (pinfunction "1_1") (pintype "passive"))
      (node (ref "C24") (pin "1") (pinfunction "1_1") (pintype "passive"))
      (node (ref "C26") (pin "1") (pinfunction "1_1") (pintype "passive"))
      (node (ref "C27") (pin "1") (pinfunction "1_1") (pintype "passive"))
      (node (ref "C28") (pin "1") (pinfunction "1_1") (pintype "passive"))
      (node (ref "C30") (pin "1") (pinfunction "1_1") (pintype "passive"))
      (node (ref "C32") (pin "1") (pinfunction "1_1") (pintype "passive"))
      (node (ref "C34") (pin "1") (pinfunction "1_1") (pintype "passive"))
      (node (ref "IC1") (pin "13") (pinfunction "VDD3_PLL2_13") (pintype "bidirectional"))
      (node (ref "IC1") (pin "18") (pinfunction "VDD3_REF_18") (pintype "bidirectional"))
      (node (ref "IC1") (pin "2") (pinfunction "VDD3_PLL1_2") (pintype "bidirectional"))
      (node (ref "IC1") (pin "27") (pinfunction "VDD3_OUT[12:13]_27") (pintype "bidirectional"))
      (node (ref "IC1") (pin "33") (pinfunction "VDD3_OUT[10:11]_33") (pintype "bidirectional"))
      (node (ref "IC1") (pin "39") (pinfunction "VDD3_OUT[8:9]_39") (pintype "bidirectional"))
      (node (ref "IC1") (pin "45") (pinfunction "VDD3_OUT[6:7]_45") (pintype "bidirectional"))
      (node (ref "IC1") (pin "51") (pinfunction "VDD3_OUT[4:5]_51") (pintype "bidirectional"))
      (node (ref "IC1") (pin "60") (pinfunction "VDD3_OUT[2:3]_60") (pintype "bidirectional"))
      (node (ref "IC1") (pin "66") (pinfunction "VDD3_OUT[0:1]_66") (pintype "bidirectional"))
      (node (ref "L10") (pin "1") (pinfunction "1_1") (pintype "passive"))
    )
    (net (code "3") (name "/+3V3_LO_1") (class "Default")
      (node (ref "C38") (pin "1") (pinfunction "1_1") (pintype "passive"))
      (node (ref "C39") (pin "1") (pinfunction "1_1") (pintype "passive"))
      (node (ref "C40") (pin "1") (pinfunction "1_1") (pintype "passive"))
      (node (ref "C45") (pin "1") (pinfunction "1_1") (pintype "passive"))
      (node (ref "C48") (pin "1") (pinfunction "1_1") (pintype "passive"))
      (node (ref "C49") (pin "1") (pinfunction "1_1") (pintype "passive"))
      (node (ref "C50") (pin "1") (pinfunction "1_1") (pintype "passive"))
      (node (ref "C72") (pin "1") (pinfunction "1_1") (pintype "passive"))
      (node (ref "C77") (pin "1") (pinfunction "1_1") (pintype "passive"))
      (node (ref "C78") (pin "1") (pinfunction "1_1") (pintype "passive"))
      (node (ref "C79") (pin "1") (pinfunction "1_1") (pintype "passive"))
      (node (ref "C80") (pin "1") (pinfunction "1_1") (pintype "passive"))
      (node (ref "C81") (pin "1") (pinfunction "1_1") (pintype "passive"))
      (node (ref "L12") (pin "1") (pinfunction "1_1") (pintype "passive"))
      (node (ref "R24") (pin "2") (pinfunction "2_2") (pintype "passive"))
      (node (ref "R25") (pin "2") (pinfunction "2_2") (pintype "passive"))
      (node (ref "R37") (pin "2") (pinfunction "2_2") (pintype "passive"))
      (node (ref "R38") (pin "2") (pinfunction "2_2") (pintype "passive"))
      (node (ref "U1") (pin "3") (pinfunction "V3_NDIV_3") (pintype "power_in"))
      (node (ref "U1") (pin "30") (pinfunction "V3_LS_30") (pintype "power_in"))
      (node (ref "U1") (pin "36") (pinfunction "V3_LDO_36") (pintype "power_in"))
      (node (ref "U1") (pin "40") (pinfunction "V3_SYNC_40") (pintype "power_in"))
      (node (ref "U1") (pin "44") (pinfunction "V3_REF_44") (pintype "power_in"))
      (node (ref "U1") (pin "45") (pinfunction "V3_PFD_45") (pintype "power_in"))
      (node (ref "U6") (pin "3") (pinfunction "V3_NDIV_3") (pintype "power_in"))
      (node (ref "U6") (pin "30") (pinfunction "V3_LS_30") (pintype "power_in"))
      (node (ref "U6") (pin "36") (pinfunction "V3_LDO_36") (pintype "power_in"))
      (node (ref "U6") (pin "40") (pinfunction "V3_SYNC_40") (pintype "power_in"))
      (node (ref "U6") (pin "44") (pinfunction "V3_REF_44") (pintype "power_in"))
      (node (ref "U6") (pin "45") (pinfunction "V3_PFD_45") (pintype "power_in"))
    )
    (net (code "4") (name "/+3V3_LO_2") (class "Default")
      (node (ref "C1") (pin "1") (pinfunction "1_1") (pintype "passive"))
      (node (ref "C47") (pin "1") (pinfunction "1_1") (pintype "passive"))
      (node (ref "C55") (pin "1") (pinfunction "1_1") (pintype "passive"))
      (node (ref "C56") (pin "1") (pinfunction "1_1") (pintype "passive"))
      (node (ref "C57") (pin "1") (pinfunction "1_1") (pintype "passive"))
      (node (ref "C58") (pin "1") (pinfunction "1_1") (pintype "passive"))
      (node (ref "C63") (pin "1") (pinfunction "1_1") (pintype "passive"))
      (node (ref "C73") (pin "1") (pinfunction "1_1") (pintype "passive"))
      (node (ref "C74") (pin "1") (pinfunction "1_1") (pintype "passive"))
      (node (ref "C75") (pin "1") (pinfunction "1_1") (pintype "passive"))
      (node (ref "C76") (pin "1") (pinfunction "1_1") (pintype "passive"))
      (node (ref "C86") (pin "1") (pinfunction "1_1") (pintype "passive"))
      (node (ref "C89") (pin "1") (pinfunction "1_1") (pintype "passive"))
      (node (ref "L1") (pin "1") (pinfunction "1_1") (pintype "passive"))
      (node (ref "L13") (pin "1") (pinfunction "1_1") (pintype "passive"))
      (node (ref "L2") (pin "1") (pinfunction "1_1") (pintype "passive"))
      (node (ref "L3") (pin "2") (pinfunction "2_2") (pintype "passive"))
      (node (ref "L4") (pin "2") (pinfunction "2_2") (pintype "passive"))
      (node (ref "L5") (pin "1") (pinfunction "1_1") (pintype "passive"))
      (node (ref "L6") (pin "2") (pinfunction "2_2") (pintype "passive"))
      (node (ref "L7") (pin "1") (pinfunction "1_1") (pintype "passive"))
      (node (ref "L8") (pin "2") (pinfunction "2_2") (pintype "passive"))
      (node (ref "U1") (pin "11") (pinfunction "V3_OUTDIV_11") (pintype "power_in"))
      (node (ref "U1") (pin "13") (pinfunction "V3_RFOUT2_13") (pintype "power_in"))
      (node (ref "U1") (pin "24") (pinfunction "V3_RFOUT1_24") (pintype "power_in"))
      (node (ref "U1") (pin "5") (pinfunction "V3_VCOB_5") (pintype "power_in"))
      (node (ref "U6") (pin "11") (pinfunction "V3_OUTDIV_11") (pintype "power_in"))
      (node (ref "U6") (pin "13") (pinfunction "V3_RFOUT2_13") (pintype "power_in"))
      (node (ref "U6") (pin "24") (pinfunction "V3_RFOUT1_24") (pintype "power_in"))
      (node (ref "U6") (pin "5") (pinfunction "V3_VCOB_5") (pintype "power_in"))
    )
    (net (code "5") (name "/+3V3_XO") (class "Default")
      (node (ref "C23") (pin "1") (pinfunction "1_1") (pintype "passive"))
      (node (ref "L9") (pin "1") (pinfunction "1_1") (pintype "passive"))
      (node (ref "R2") (pin "2") (pinfunction "2_2") (pintype "passive"))
      (node (ref "X4") (pin "3") (pinfunction "SUPPLY_VOLTAGE_3") (pintype "passive"))
      (node (ref "X5") (pin "4") (pinfunction "VDD_4") (pintype "power_in"))
      (node (ref "X6") (pin "4") (pinfunction "VDD_4") (pintype "power_in"))
    )
    (net (code "6") (name "/+5V0_LO") (class "Default")
      (node (ref "C51") (pin "1") (pinfunction "1_1") (pintype "passive"))
      (node (ref "FB1") (pin "1") (pinfunction "1_1") (pintype "passive"))
      (node (ref "FB2") (pin "1") (pinfunction "1_1") (pintype "passive"))
      (node (ref "FB3") (pin "2") (pinfunction "2_2") (pintype "passive"))
      (node (ref "FB4") (pin "2") (pinfunction "2_2") (pintype "passive"))
      (node (ref "X15") (pin "1") (pinfunction "S_1") (pintype "passive"))
    )
    (net (code "7") (name "/10MHZ_OUT") (class "Default")
      (node (ref "IC1") (pin "3") (pinfunction "REFA_3") (pintype "bidirectional"))
      (node (ref "X4") (pin "4") (pinfunction "OUTPUT_4") (pintype "output"))
    )
    (net (code "8") (name "/100MHZ_OUT") (class "Default")
      (node (ref "IC1") (pin "5") (pinfunction "REFB_5") (pintype "bidirectional"))
      (node (ref "X5") (pin "3") (pinfunction "OUT_3") (pintype "output"))
    )
    (net (code "9") (name "/AD9523_CS") (class "Default")
      (node (ref "JP1") (pin "5") (pinfunction "5_5") (pintype "passive"))
      (node (ref "R10") (pin "1") (pinfunction "1_1") (pintype "passive"))
    )
    (net (code "10") (name "/AD9523_EEPROM_SEL") (class "Default")
      (node (ref "IC1") (pin "57") (pinfunction "EEPROM_SEL_57") (pintype "bidirectional"))
      (node (ref "JP1") (pin "11") (pinfunction "11_11") (pintype "passive"))
    )
    (net (code "11") (name "/AD9523_OUT0_N") (class "Default")
      (node (ref "C11") (pin "2") (pinfunction "2_2") (pintype "passive"))
      (node (ref "IC1") (pin "67") (pinfunction "~{OUT0}_67") (pintype "bidirectional"))
    )
    (net (code "12") (name "/AD9523_OUT0_P") (class "Default")
      (node (ref "C12") (pin "2") (pinfunction "2_2") (pintype "passive"))
      (node (ref "IC1") (pin "68") (pinfunction "OUT0_68") (pintype "bidirectional"))
    )
    (net (code "13") (name "/AD9523_OUT1_N") (class "Default")
      (node (ref "C68") (pin "2") (pinfunction "2_2") (pintype "passive"))
      (node (ref "IC1") (pin "64") (pinfunction "~{OUT1}_64") (pintype "bidirectional"))
    )
    (net (code "14") (name "/AD9523_OUT1_P") (class "Default")
      (node (ref "C69") (pin "2") (pinfunction "2_2") (pintype "passive"))
      (node (ref "IC1") (pin "65") (pinfunction "OUT1_65") (pintype "bidirectional"))
    )
    (net (code "15") (name "/AD9523_OUT2+") (class "Default")
      (node (ref "IC1") (pin "62") (pinfunction "OUT2_62") (pintype "bidirectional"))
    )
    (net (code "16") (name "/AD9523_OUT2-") (class "Default")
      (node (ref "IC1") (pin "61") (pinfunction "~{OUT2}_61") (pintype "bidirectional"))
    )
    (net (code "17") (name "/AD9523_OUT3+") (class "Default")
      (node (ref "IC1") (pin "59") (pinfunction "OUT3_59") (pintype "bidirectional"))
    )
    (net (code "18") (name "/AD9523_OUT3-") (class "Default")
      (node (ref "IC1") (pin "58") (pinfunction "~{OUT3}_58") (pintype "bidirectional"))
    )
    (net (code "19") (name "/AD9523_OUT4_N") (class "Default")
      (node (ref "IC1") (pin "52") (pinfunction "~{OUT4}_52") (pintype "bidirectional"))
      (node (ref "J3") (pin "2") (pinfunction "2_2") (pintype "passive"))
    )
    (net (code "20") (name "/AD9523_OUT4_P") (class "Default")
      (node (ref "IC1") (pin "53") (pinfunction "OUT4_53") (pintype "bidirectional"))
      (node (ref "J3") (pin "1") (pinfunction "1_1") (pintype "passive"))
    )
    (net (code "21") (name "/AD9523_OUT5_N") (class "Default")
      (node (ref "IC1") (pin "49") (pinfunction "~{OUT5}_49") (pintype "bidirectional"))
      (node (ref "J4") (pin "2") (pinfunction "2_2") (pintype "passive"))
    )
    (net (code "22") (name "/AD9523_OUT5_P") (class "Default")
      (node (ref "IC1") (pin "50") (pinfunction "OUT5_50") (pintype "bidirectional"))
      (node (ref "J4") (pin "1") (pinfunction "1_1") (pintype "passive"))
    )
    (net (code "23") (name "/AD9523_OUT6+") (class "Default")
      (node (ref "C15") (pin "2") (pinfunction "2_2") (pintype "passive"))
      (node (ref "J7") (pin "1") (pinfunction "1_1") (pintype "bidirectional"))
    )
    (net (code "24") (name "/AD9523_OUT7+") (class "Default")
      (node (ref "IC1") (pin "44") (pinfunction "OUT7_44") (pintype "bidirectional"))
      (node (ref "J8") (pin "1") (pinfunction "1_1") (pintype "bidirectional"))
    )
    (net (code "25") (name "/AD9523_OUT8_N") (class "Default")
      (node (ref "C70") (pin "2") (pinfunction "2_2") (pintype "passive"))
      (node (ref "IC1") (pin "40") (pinfunction "~{OUT8}_40") (pintype "bidirectional"))
    )
    (net (code "26") (name "/AD9523_OUT8_P") (class "Default")
      (node (ref "C71") (pin "2") (pinfunction "2_2") (pintype "passive"))
      (node (ref "IC1") (pin "41") (pinfunction "OUT8_41") (pintype "bidirectional"))
    )
    (net (code "27") (name "/AD9523_OUT9_N") (class "Default")
      (node (ref "C13") (pin "2") (pinfunction "2_2") (pintype "passive"))
      (node (ref "IC1") (pin "37") (pinfunction "~{OUT9}_37") (pintype "bidirectional"))
    )
    (net (code "28") (name "/AD9523_OUT9_P") (class "Default")
      (node (ref "C14") (pin "2") (pinfunction "2_2") (pintype "passive"))
      (node (ref "IC1") (pin "38") (pinfunction "OUT9_38") (pintype "bidirectional"))
    )
    (net (code "29") (name "/AD9523_OUT10+") (class "Default")
      (node (ref "IC1") (pin "35") (pinfunction "OUT10_35") (pintype "bidirectional"))
      (node (ref "R40") (pin "1") (pinfunction "1_1") (pintype "passive"))
    )
    (net (code "30") (name "/AD9523_OUT11+") (class "Default")
      (node (ref "IC1") (pin "32") (pinfunction "OUT11_32") (pintype "bidirectional"))
      (node (ref "R41") (pin "1") (pinfunction "1_1") (pintype "passive"))
    )
    (net (code "31") (name "/AD9523_PD") (class "Default")
      (node (ref "IC1") (pin "15") (pinfunction "~{PD}_15") (pintype "bidirectional"))
      (node (ref "JP1") (pin "1") (pinfunction "1_1") (pintype "passive"))
    )
    (net (code "32") (name "/AD9523_REF_SEL") (class "Default")
      (node (ref "IC1") (pin "16") (pinfunction "REF_SEL_16") (pintype "bidirectional"))
      (node (ref "JP1") (pin "2") (pinfunction "2_2") (pintype "passive"))
    )
    (net (code "33") (name "/AD9523_RESET") (class "Default")
      (node (ref "IC1") (pin "19") (pinfunction "~{RESET}_19") (pintype "bidirectional"))
      (node (ref "JP1") (pin "4") (pinfunction "4_4") (pintype "passive"))
    )
    (net (code "34") (name "/AD9523_SCLK") (class "Default")
      (node (ref "JP1") (pin "6") (pinfunction "6_6") (pintype "passive"))
      (node (ref "R6") (pin "1") (pinfunction "1_1") (pintype "passive"))
    )
    (net (code "35") (name "/AD9523_SDIO") (class "Default")
      (node (ref "JP1") (pin "7") (pinfunction "7_7") (pintype "passive"))
      (node (ref "R8") (pin "1") (pinfunction "1_1") (pintype "passive"))
    )
    (net (code "36") (name "/AD9523_SDO") (class "Default")
      (node (ref "IC1") (pin "23") (pinfunction "SDO_23") (pintype "bidirectional"))
      (node (ref "JP1") (pin "8") (pinfunction "8_8") (pintype "passive"))
    )
    (net (code "37") (name "/AD9523_STATUS0") (class "Default")
      (node (ref "IC1") (pin "56") (pinfunction "STATUS0/SP0_56") (pintype "bidirectional"))
      (node (ref "JP1") (pin "9") (pinfunction "9_9") (pintype "passive"))
    )
    (net (code "38") (name "/AD9523_STATUS1") (class "Default")
      (node (ref "IC1") (pin "55") (pinfunction "STATUS1/SPI_55") (pintype "bidirectional"))
      (node (ref "JP1") (pin "10") (pinfunction "10_10") (pintype "passive"))
    )
    (net (code "39") (name "/AD9523_SYNC") (class "Default")
      (node (ref "IC1") (pin "17") (pinfunction "~{SYNC}_17") (pintype "bidirectional"))
      (node (ref "JP1") (pin "3") (pinfunction "3_3") (pintype "passive"))
    )
    (net (code "40") (name "/ADF4382_RX_CE") (class "Default")
      (node (ref "JP2") (pin "10") (pinfunction "10_10") (pintype "passive"))
      (node (ref "R38") (pin "1") (pinfunction "1_1") (pintype "passive"))
      (node (ref "U6") (pin "31") (pinfunction "CE_31") (pintype "input"))
    )
    (net (code "41") (name "/ADF4382_RX_CS") (class "Default")
      (node (ref "JP2") (pin "9") (pinfunction "9_9") (pintype "passive"))
      (node (ref "R37") (pin "1") (pinfunction "1_1") (pintype "passive"))
      (node (ref "U6") (pin "32") (pinfunction "CSB_32") (pintype "input"))
    )
    (net (code "42") (name "/ADF4382_RX_DELADJ") (class "Default")
      (node (ref "JP2") (pin "12") (pinfunction "12_12") (pintype "passive"))
      (node (ref "R35") (pin "2") (pinfunction "2_2") (pintype "passive"))
      (node (ref "U6") (pin "28") (pinfunction "DELADJ_28") (pintype "input"))
    )
    (net (code "43") (name "/ADF4382_RX_DELSTR") (class "Default")
      (node (ref "JP2") (pin "11") (pinfunction "11_11") (pintype "passive"))
      (node (ref "R36") (pin "2") (pinfunction "2_2") (pintype "passive"))
      (node (ref "U6") (pin "29") (pinfunction "DELSTR_29") (pintype "input"))
    )
    (net (code "44") (name "/ADF4382_RX_LKDET") (class "Default")
      (node (ref "JP2") (pin "13") (pinfunction "13_13") (pintype "passive"))
      (node (ref "R34") (pin "2") (pinfunction "2_2") (pintype "passive"))
      (node (ref "U6") (pin "27") (pinfunction "LKDET_27") (pintype "output"))
    )
    (net (code "45") (name "/ADF4382_RX_SYNC_N") (class "Default")
      (node (ref "C70") (pin "1") (pinfunction "1_1") (pintype "passive"))
      (node (ref "R26") (pin "2") (pinfunction "2_2") (pintype "passive"))
      (node (ref "U6") (pin "39") (pinfunction "SYNCN_39") (pintype "input"))
    )
    (net (code "46") (name "/ADF4382_RX_SYNC_P") (class "Default")
      (node (ref "C71") (pin "1") (pinfunction "1_1") (pintype "passive"))
      (node (ref "R26") (pin "1") (pinfunction "1_1") (pintype "passive"))
      (node (ref "U6") (pin "38") (pinfunction "SYNCP_38") (pintype "input"))
    )
    (net (code "47") (name "/ADF4382_SCLK") (class "Default")
      (node (ref "JP2") (pin "2") (pinfunction "2_2") (pintype "passive"))
      (node (ref "U1") (pin "34") (pinfunction "SCLK_34") (pintype "input"))
      (node (ref "U6") (pin "34") (pinfunction "SCLK_34") (pintype "input"))
    )
    (net (code "48") (name "/ADF4382_SDIO") (class "Default")
      (node (ref "JP2") (pin "3") (pinfunction "3_3") (pintype "passive"))
      (node (ref "U1") (pin "33") (pinfunction "SDIO_33") (pintype "bidirectional"))
      (node (ref "U6") (pin "33") (pinfunction "SDIO_33") (pintype "bidirectional"))
    )
    (net (code "49") (name "/ADF4382_SDO") (class "Default")
      (node (ref "JP2") (pin "1") (pinfunction "1_1") (pintype "passive"))
      (node (ref "U1") (pin "35") (pinfunction "SDO_35") (pintype "output"))
      (node (ref "U6") (pin "35") (pinfunction "SDO_35") (pintype "output"))
    )
    (net (code "50") (name "/ADF4382_TX_CE") (class "Default")
      (node (ref "JP2") (pin "5") (pinfunction "5_5") (pintype "passive"))
      (node (ref "R25") (pin "1") (pinfunction "1_1") (pintype "passive"))
      (node (ref "U1") (pin "31") (pinfunction "CE_31") (pintype "input"))
    )
    (net (code "51") (name "/ADF4382_TX_CS") (class "Default")
      (node (ref "JP2") (pin "4") (pinfunction "4_4") (pintype "passive"))
      (node (ref "R24") (pin "1") (pinfunction "1_1") (pintype "passive"))
      (node (ref "U1") (pin "32") (pinfunction "CSB_32") (pintype "input"))
    )
    (net (code "52") (name "/ADF4382_TX_DELADJ") (class "Default")
      (node (ref "JP2") (pin "7") (pinfunction "7_7") (pintype "passive"))
      (node (ref "R22") (pin "2") (pinfunction "2_2") (pintype "passive"))
      (node (ref "U1") (pin "28") (pinfunction "DELADJ_28") (pintype "input"))
    )
    (net (code "53") (name "/ADF4382_TX_DELSTR") (class "Default")
      (node (ref "JP2") (pin "6") (pinfunction "6_6") (pintype "passive"))
      (node (ref "R23") (pin "2") (pinfunction "2_2") (pintype "passive"))
      (node (ref "U1") (pin "29") (pinfunction "DELSTR_29") (pintype "input"))
    )
    (net (code "54") (name "/ADF4382_TX_LKDET") (class "Default")
      (node (ref "JP2") (pin "8") (pinfunction "8_8") (pintype "passive"))
      (node (ref "R21") (pin "2") (pinfunction "2_2") (pintype "passive"))
      (node (ref "U1") (pin "27") (pinfunction "LKDET_27") (pintype "output"))
    )
    (net (code "55") (name "/ADF4382_TX_SYNC_N") (class "Default")
      (node (ref "C13") (pin "1") (pinfunction "1_1") (pintype "passive"))
      (node (ref "R13") (pin "2") (pinfunction "2_2") (pintype "passive"))
      (node (ref "U1") (pin "39") (pinfunction "SYNCN_39") (pintype "input"))
    )
    (net (code "56") (name "/ADF4382_TX_SYNC_P") (class "Default")
      (node (ref "C14") (pin "1") (pinfunction "1_1") (pintype "passive"))
      (node (ref "R13") (pin "1") (pinfunction "1_1") (pintype "passive"))
      (node (ref "U1") (pin "38") (pinfunction "SYNCP_38") (pintype "input"))
    )
    (net (code "57") (name "/OSC_CTRL") (class "Default")
      (node (ref "IC1") (pin "8") (pinfunction "OSC_CTRL_8") (pintype "bidirectional"))
      (node (ref "R4") (pin "2") (pinfunction "2_2") (pintype "passive"))
    )
    (net (code "58") (name "/RX_RFOUT_1_N") (class "Default")
      (node (ref "C87") (pin "1") (pinfunction "1_1") (pintype "passive"))
      (node (ref "L5") (pin "2") (pinfunction "2_2") (pintype "passive"))
      (node (ref "U6") (pin "20") (pinfunction "RFOUT1N_20") (pintype "output"))
    )
    (net (code "59") (name "/RX_RFOUT_1_P") (class "Default")
      (node (ref "C88") (pin "1") (pinfunction "1_1") (pintype "passive"))
      (node (ref "L6") (pin "1") (pinfunction "1_1") (pintype "passive"))
      (node (ref "U6") (pin "22") (pinfunction "RFOUT1P_22") (pintype "output"))
    )
    (net (code "60") (name "/RX_RFOUT_2_N") (class "Default")
      (node (ref "C90") (pin "1") (pinfunction "1_1") (pintype "passive"))
      (node (ref "L7") (pin "2") (pinfunction "2_2") (pintype "passive"))
      (node (ref "U6") (pin "15") (pinfunction "RFOUT2N_15") (pintype "output"))
    )
    (net (code "61") (name "/RX_RFOUT_2_P") (class "Default")
      (node (ref "C91") (pin "1") (pinfunction "1_1") (pintype "passive"))
      (node (ref "L8") (pin "1") (pinfunction "1_1") (pintype "passive"))
      (node (ref "U6") (pin "17") (pinfunction "RFOUT2P_17") (pintype "output"))
    )
    (net (code "62") (name "/TX_RFOUT_1_N") (class "Default")
      (node (ref "C64") (pin "1") (pinfunction "1_1") (pintype "passive"))
      (node (ref "L2") (pin "2") (pinfunction "2_2") (pintype "passive"))
      (node (ref "U1") (pin "20") (pinfunction "RFOUT1N_20") (pintype "output"))
    )
    (net (code "63") (name "/TX_RFOUT_1_P") (class "Default")
      (node (ref "C65") (pin "1") (pinfunction "1_1") (pintype "passive"))
      (node (ref "L3") (pin "1") (pinfunction "1_1") (pintype "passive"))
      (node (ref "U1") (pin "22") (pinfunction "RFOUT1P_22") (pintype "output"))
    )
    (net (code "64") (name "/TX_RFOUT_2_N") (class "Default")
      (node (ref "C66") (pin "1") (pinfunction "1_1") (pintype "passive"))
      (node (ref "L1") (pin "2") (pinfunction "2_2") (pintype "passive"))
      (node (ref "U1") (pin "15") (pinfunction "RFOUT2N_15") (pintype "output"))
    )
    (net (code "65") (name "/TX_RFOUT_2_P") (class "Default")
      (node (ref "C67") (pin "1") (pinfunction "1_1") (pintype "passive"))
      (node (ref "L4") (pin "1") (pinfunction "1_1") (pintype "passive"))
      (node (ref "U1") (pin "17") (pinfunction "RFOUT2P_17") (pintype "output"))
    )
    (net (code "66") (name "/VCXO_OUT") (class "Default")
      (node (ref "IC1") (pin "9") (pinfunction "OSC_IN_9") (pintype "bidirectional"))
      (node (ref "X6") (pin "3") (pinfunction "OUT_3") (pintype "output"))
    )
    (net (code "67") (name "GND") (class "Default")
      (node (ref "C1") (pin "2") (pinfunction "2_2") (pintype "passive"))
      (node (ref "C10") (pin "1") (pinfunction "1_1") (pintype "passive"))
      (node (ref "C16") (pin "2") (pinfunction "2_2") (pintype "passive"))
      (node (ref "C18") (pin "2") (pinfunction "2_2") (pintype "passive"))
      (node (ref "C2") (pin "2") (pinfunction "2_2") (pintype "passive"))
      (node (ref "C20") (pin "2") (pinfunction "2_2") (pintype "passive"))
      (node (ref "C21") (pin "2") (pinfunction "2_2") (pintype "passive"))
      (node (ref "C22") (pin "2") (pinfunction "2_2") (pintype "passive"))
      (node (ref "C23") (pin "2") (pinfunction "2_2") (pintype "passive"))
      (node (ref "C24") (pin "2") (pinfunction "2_2") (pintype "passive"))
      (node (ref "C25") (pin "2") (pinfunction "2_2") (pintype "passive"))
      (node (ref "C26") (pin "2") (pinfunction "2_2") (pintype "passive"))
      (node (ref "C27") (pin "2") (pinfunction "2_2") (pintype "passive"))
      (node (ref "C28") (pin "2") (pinfunction "2_2") (pintype "passive"))
      (node (ref "C29") (pin "2") (pinfunction "2_2") (pintype "passive"))
      (node (ref "C3") (pin "1") (pinfunction "1_1") (pintype "passive"))
      (node (ref "C30") (pin "2") (pinfunction "2_2") (pintype "passive"))
      (node (ref "C31") (pin "2") (pinfunction "2_2") (pintype "passive"))
      (node (ref "C32") (pin "2") (pinfunction "2_2") (pintype "passive"))
      (node (ref "C33") (pin "2") (pinfunction "2_2") (pintype "passive"))
      (node (ref "C34") (pin "2") (pinfunction "2_2") (pintype "passive"))
      (node (ref "C35") (pin "2") (pinfunction "2_2") (pintype "passive"))
      (node (ref "C36") (pin "2") (pinfunction "2_2") (pintype "passive"))
      (node (ref "C37") (pin "2") (pinfunction "2_2") (pintype "passive"))
      (node (ref "C38") (pin "2") (pinfunction "2_2") (pintype "passive"))
      (node (ref "C39") (pin "2") (pinfunction "2_2") (pintype "passive"))
      (node (ref "C4") (pin "1") (pinfunction "1_1") (pintype "passive"))
      (node (ref "C40") (pin "2") (pinfunction "2_2") (pintype "passive"))
      (node (ref "C41") (pin "2") (pinfunction "2_2") (pintype "passive"))
      (node (ref "C42") (pin "2") (pinfunction "2_2") (pintype "passive"))
      (node (ref "C43") (pin "2") (pinfunction "2_2") (pintype "passive"))
      (node (ref "C44") (pin "2") (pinfunction "2_2") (pintype "passive"))
      (node (ref "C45") (pin "2") (pinfunction "2_2") (pintype "passive"))
      (node (ref "C46") (pin "2") (pinfunction "2_2") (pintype "passive"))
      (node (ref "C47") (pin "2") (pinfunction "2_2") (pintype "passive"))
      (node (ref "C48") (pin "2") (pinfunction "2_2") (pintype "passive"))
      (node (ref "C49") (pin "2") (pinfunction "2_2") (pintype "passive"))
      (node (ref "C5") (pin "1") (pinfunction "1_1") (pintype "passive"))
      (node (ref "C50") (pin "2") (pinfunction "2_2") (pintype "passive"))
      (node (ref "C51") (pin "2") (pinfunction "2_2") (pintype "passive"))
      (node (ref "C55") (pin "2") (pinfunction "2_2") (pintype "passive"))
      (node (ref "C56") (pin "2") (pinfunction "2_2") (pintype "passive"))
      (node (ref "C57") (pin "2") (pinfunction "2_2") (pintype "passive"))
      (node (ref "C58") (pin "2") (pinfunction "2_2") (pintype "passive"))
      (node (ref "C59") (pin "1") (pinfunction "1_1") (pintype "passive"))
      (node (ref "C6") (pin "1") (pinfunction "1_1") (pintype "passive"))
      (node (ref "C60") (pin "2") (pinfunction "2_2") (pintype "passive"))
      (node (ref "C61") (pin "2") (pinfunction "2_2") (pintype "passive"))
      (node (ref "C62") (pin "2") (pinfunction "2_2") (pintype "passive"))
      (node (ref "C63") (pin "2") (pinfunction "2_2") (pintype "passive"))
      (node (ref "C7") (pin "1") (pinfunction "1_1") (pintype "passive"))
      (node (ref "C72") (pin "2") (pinfunction "2_2") (pintype "passive"))
      (node (ref "C73") (pin "2") (pinfunction "2_2") (pintype "passive"))
      (node (ref "C74") (pin "2") (pinfunction "2_2") (pintype "passive"))
      (node (ref "C75") (pin "2") (pinfunction "2_2") (pintype "passive"))
      (node (ref "C76") (pin "2") (pinfunction "2_2") (pintype "passive"))
      (node (ref "C77") (pin "2") (pinfunction "2_2") (pintype "passive"))
      (node (ref "C78") (pin "2") (pinfunction "2_2") (pintype "passive"))
      (node (ref "C79") (pin "2") (pinfunction "2_2") (pintype "passive"))
      (node (ref "C80") (pin "2") (pinfunction "2_2") (pintype "passive"))
      (node (ref "C81") (pin "2") (pinfunction "2_2") (pintype "passive"))
      (node (ref "C82") (pin "1") (pinfunction "1_1") (pintype "passive"))
      (node (ref "C83") (pin "2") (pinfunction "2_2") (pintype "passive"))
      (node (ref "C84") (pin "2") (pinfunction "2_2") (pintype "passive"))
      (node (ref "C85") (pin "2") (pinfunction "2_2") (pintype "passive"))
      (node (ref "C86") (pin "2") (pinfunction "2_2") (pintype "passive"))
      (node (ref "C89") (pin "2") (pinfunction "2_2") (pintype "passive"))
      (node (ref "C9") (pin "1") (pinfunction "1_1") (pintype "passive"))
      (node (ref "D1") (pin "C") (pinfunction "C_C") (pintype "passive"))
      (node (ref "D2") (pin "C") (pinfunction "C_C") (pintype "passive"))
      (node (ref "IC1") (pin "73") (pinfunction "EP_73") (pintype "bidirectional"))
      (node (ref "J1") (pin "2") (pinfunction "2_2") (pintype "bidirectional"))
      (node (ref "J1") (pin "3") (pinfunction "3_3") (pintype "bidirectional"))
      (node (ref "J1") (pin "4") (pinfunction "4_4") (pintype "bidirectional"))
      (node (ref "J1") (pin "5") (pinfunction "5_5") (pintype "bidirectional"))
      (node (ref "J10") (pin "2") (pinfunction "2_2") (pintype "bidirectional"))
      (node (ref "J10") (pin "3") (pinfunction "3_3") (pintype "bidirectional"))
      (node (ref "J10") (pin "4") (pinfunction "4_4") (pintype "bidirectional"))
      (node (ref "J10") (pin "5") (pinfunction "5_5") (pintype "bidirectional"))
      (node (ref "J11") (pin "2") (pinfunction "2_2") (pintype "bidirectional"))
      (node (ref "J11") (pin "3") (pinfunction "3_3") (pintype "bidirectional"))
      (node (ref "J11") (pin "4") (pinfunction "4_4") (pintype "bidirectional"))
      (node (ref "J11") (pin "5") (pinfunction "5_5") (pintype "bidirectional"))
      (node (ref "J12") (pin "2") (pinfunction "2_2") (pintype "bidirectional"))
      (node (ref "J12") (pin "3") (pinfunction "3_3") (pintype "bidirectional"))
      (node (ref "J12") (pin "4") (pinfunction "4_4") (pintype "bidirectional"))
      (node (ref "J12") (pin "5") (pinfunction "5_5") (pintype "bidirectional"))
      (node (ref "J13") (pin "2") (pinfunction "2_2") (pintype "bidirectional"))
      (node (ref "J13") (pin "3") (pinfunction "3_3") (pintype "bidirectional"))
      (node (ref "J13") (pin "4") (pinfunction "4_4") (pintype "bidirectional"))
      (node (ref "J13") (pin "5") (pinfunction "5_5") (pintype "bidirectional"))
      (node (ref "J2") (pin "2") (pinfunction "2_2") (pintype "bidirectional"))
      (node (ref "J2") (pin "3") (pinfunction "3_3") (pintype "bidirectional"))
      (node (ref "J2") (pin "4") (pinfunction "4_4") (pintype "bidirectional"))
      (node (ref "J2") (pin "5") (pinfunction "5_5") (pintype "bidirectional"))
      (node (ref "J5") (pin "2") (pinfunction "2_2") (pintype "bidirectional"))
      (node (ref "J5") (pin "3") (pinfunction "3_3") (pintype "bidirectional"))
      (node (ref "J5") (pin "4") (pinfunction "4_4") (pintype "bidirectional"))
      (node (ref "J5") (pin "5") (pinfunction "5_5") (pintype "bidirectional"))
      (node (ref "J6") (pin "2") (pinfunction "2_2") (pintype "bidirectional"))
      (node (ref "J6") (pin "3") (pinfunction "3_3") (pintype "bidirectional"))
      (node (ref "J6") (pin "4") (pinfunction "4_4") (pintype "bidirectional"))
      (node (ref "J6") (pin "5") (pinfunction "5_5") (pintype "bidirectional"))
      (node (ref "J7") (pin "2") (pinfunction "2_2") (pintype "bidirectional"))
      (node (ref "J7") (pin "3") (pinfunction "3_3") (pintype "bidirectional"))
      (node (ref "J7") (pin "4") (pinfunction "4_4") (pintype "bidirectional"))
      (node (ref "J7") (pin "5") (pinfunction "5_5") (pintype "bidirectional"))
      (node (ref "J8") (pin "2") (pinfunction "2_2") (pintype "bidirectional"))
      (node (ref "J8") (pin "3") (pinfunction "3_3") (pintype "bidirectional"))
      (node (ref "J8") (pin "4") (pinfunction "4_4") (pintype "bidirectional"))
      (node (ref "J8") (pin "5") (pinfunction "5_5") (pintype "bidirectional"))
      (node (ref "J9") (pin "2") (pinfunction "2_2") (pintype "bidirectional"))
      (node (ref "J9") (pin "3") (pinfunction "3_3") (pintype "bidirectional"))
      (node (ref "J9") (pin "4") (pinfunction "4_4") (pintype "bidirectional"))
      (node (ref "J9") (pin "5") (pinfunction "5_5") (pintype "bidirectional"))
      (node (ref "JP1") (pin "12") (pinfunction "12_12") (pintype "passive"))
      (node (ref "JP2") (pin "14") (pinfunction "14_14") (pintype "passive"))
      (node (ref "R11") (pin "2") (pinfunction "2_2") (pintype "passive"))
      (node (ref "R22") (pin "1") (pinfunction "1_1") (pintype "passive"))
      (node (ref "R23") (pin "1") (pinfunction "1_1") (pintype "passive"))
      (node (ref "R3") (pin "1") (pinfunction "1_1") (pintype "passive"))
      (node (ref "R35") (pin "1") (pinfunction "1_1") (pintype "passive"))
      (node (ref "R36") (pin "1") (pinfunction "1_1") (pintype "passive"))
      (node (ref "R7") (pin "2") (pinfunction "2_2") (pintype "passive"))
      (node (ref "R9") (pin "2") (pinfunction "2_2") (pintype "passive"))
      (node (ref "U1") (pin "1") (pinfunction "GND_2_1") (pintype "passive"))
      (node (ref "U1") (pin "10") (pinfunction "GND_5_10") (pintype "passive"))
      (node (ref "U1") (pin "12") (pinfunction "GND_6_12") (pintype "passive"))
      (node (ref "U1") (pin "14") (pinfunction "GND_7_14") (pintype "passive"))
      (node (ref "U1") (pin "16") (pinfunction "GND_8_16") (pintype "passive"))
      (node (ref "U1") (pin "18") (pinfunction "GND_9_18") (pintype "passive"))
      (node (ref "U1") (pin "19") (pinfunction "GND_10_19") (pintype "passive"))
      (node (ref "U1") (pin "2") (pinfunction "GND_3_2") (pintype "passive"))
      (node (ref "U1") (pin "21") (pinfunction "GND_11_21") (pintype "passive"))
      (node (ref "U1") (pin "23") (pinfunction "GND_12_23") (pintype "passive"))
      (node (ref "U1") (pin "25") (pinfunction "GND_13_25") (pintype "passive"))
      (node (ref "U1") (pin "26") (pinfunction "GND_14_26") (pintype "passive"))
      (node (ref "U1") (pin "4") (pinfunction "GND_4_4") (pintype "passive"))
      (node (ref "U1") (pin "41") (pinfunction "GND_15_41") (pintype "passive"))
      (node (ref "U1") (pin "48") (pinfunction "GND_16_48") (pintype "passive"))
      (node (ref "U1") (pin "49") (pinfunction "GND_17_49") (pintype "passive"))
      (node (ref "U1") (pin "50") (pinfunction "GND_18_50") (pintype "passive"))
      (node (ref "U1") (pin "51") (pinfunction "GND_19_51") (pintype "passive"))
      (node (ref "U1") (pin "52") (pinfunction "GND_52") (pintype "passive"))
      (node (ref "U10") (pin "3") (pinfunction "GND_2_3") (pintype "passive"))
      (node (ref "U10") (pin "4") (pinfunction "GND_4") (pintype "passive"))
      (node (ref "U2") (pin "1") (pinfunction "EXTERNAL_GND_2_1") (pintype "passive"))
      (node (ref "U2") (pin "10") (pinfunction "EXTERNAL_GND_5_10") (pintype "passive"))
      (node (ref "U2") (pin "13") (pinfunction "EXTERNAL_GND_13") (pintype "passive"))
      (node (ref "U2") (pin "3") (pinfunction "EXTERNAL_GND_3_3") (pintype "passive"))
      (node (ref "U2") (pin "6") (pinfunction "EXTERNAL_GND_4_6") (pintype "passive"))
      (node (ref "U3") (pin "1") (pinfunction "EXTERNAL_GND_2_1") (pintype "passive"))
      (node (ref "U3") (pin "10") (pinfunction "EXTERNAL_GND_5_10") (pintype "passive"))
      (node (ref "U3") (pin "13") (pinfunction "EXTERNAL_GND_13") (pintype "passive"))
      (node (ref "U3") (pin "3") (pinfunction "EXTERNAL_GND_3_3") (pintype "passive"))
      (node (ref "U3") (pin "6") (pinfunction "EXTERNAL_GND_4_6") (pintype "passive"))
      (node (ref "U4") (pin "3") (pinfunction "GND_2_3") (pintype "passive"))
      (node (ref "U4") (pin "4") (pinfunction "GND_4") (pintype "passive"))
      (node (ref "U5") (pin "3") (pinfunction "GND_2_3") (pintype "passive"))
      (node (ref "U5") (pin "4") (pinfunction "GND_4") (pintype "passive"))
      (node (ref "U6") (pin "1") (pinfunction "GND_2_1") (pintype "passive"))
      (node (ref "U6") (pin "10") (pinfunction "GND_5_10") (pintype "passive"))
      (node (ref "U6") (pin "12") (pinfunction "GND_6_12") (pintype "passive"))
      (node (ref "U6") (pin "14") (pinfunction "GND_7_14") (pintype "passive"))
      (node (ref "U6") (pin "16") (pinfunction "GND_8_16") (pintype "passive"))
      (node (ref "U6") (pin "18") (pinfunction "GND_9_18") (pintype "passive"))
      (node (ref "U6") (pin "19") (pinfunction "GND_10_19") (pintype "passive"))
      (node (ref "U6") (pin "2") (pinfunction "GND_3_2") (pintype "passive"))
      (node (ref "U6") (pin "21") (pinfunction "GND_11_21") (pintype "passive"))
      (node (ref "U6") (pin "23") (pinfunction "GND_12_23") (pintype "passive"))
      (node (ref "U6") (pin "25") (pinfunction "GND_13_25") (pintype "passive"))
      (node (ref "U6") (pin "26") (pinfunction "GND_14_26") (pintype "passive"))
      (node (ref "U6") (pin "4") (pinfunction "GND_4_4") (pintype "passive"))
      (node (ref "U6") (pin "41") (pinfunction "GND_15_41") (pintype "passive"))
      (node (ref "U6") (pin "48") (pinfunction "GND_16_48") (pintype "passive"))
      (node (ref "U6") (pin "49") (pinfunction "GND_17_49") (pintype "passive"))
      (node (ref "U6") (pin "50") (pinfunction "GND_18_50") (pintype "passive"))
      (node (ref "U6") (pin "51") (pinfunction "GND_19_51") (pintype "passive"))
      (node (ref "U6") (pin "52") (pinfunction "GND_52") (pintype "passive"))
      (node (ref "U7") (pin "1") (pinfunction "EXTERNAL_GND_2_1") (pintype "passive"))
      (node (ref "U7") (pin "10") (pinfunction "EXTERNAL_GND_5_10") (pintype "passive"))
      (node (ref "U7") (pin "13") (pinfunction "EXTERNAL_GND_13") (pintype "passive"))
      (node (ref "U7") (pin "3") (pinfunction "EXTERNAL_GND_3_3") (pintype "passive"))
      (node (ref "U7") (pin "6") (pinfunction "EXTERNAL_GND_4_6") (pintype "passive"))
      (node (ref "U8") (pin "3") (pinfunction "GND_2_3") (pintype "passive"))
      (node (ref "U8") (pin "4") (pinfunction "GND_4") (pintype "passive"))
      (node (ref "U9") (pin "1") (pinfunction "EXTERNAL_GND_2_1") (pintype "passive"))
      (node (ref "U9") (pin "10") (pinfunction "EXTERNAL_GND_5_10") (pintype "passive"))
      (node (ref "U9") (pin "13") (pinfunction "EXTERNAL_GND_13") (pintype "passive"))
      (node (ref "U9") (pin "3") (pinfunction "EXTERNAL_GND_3_3") (pintype "passive"))
      (node (ref "U9") (pin "6") (pinfunction "EXTERNAL_GND_4_6") (pintype "passive"))
      (node (ref "X10") (pin "2") (pinfunction "S_2") (pintype "passive"))
      (node (ref "X11") (pin "2") (pinfunction "S_2") (pintype "passive"))
      (node (ref "X12") (pin "2") (pinfunction "S_2") (pintype "passive"))
      (node (ref "X13") (pin "2") (pinfunction "S_2") (pintype "passive"))
      (node (ref "X14") (pin "2") (pinfunction "S_2") (pintype "passive"))
      (node (ref "X15") (pin "2") (pinfunction "S_2") (pintype "passive"))
      (node (ref "X4") (pin "5") (pinfunction "GROUND_5") (pintype "passive"))
      (node (ref "X5") (pin "2") (pinfunction "GND_2") (pintype "passive"))
      (node (ref "X6") (pin "2") (pinfunction "GND_2") (pintype "passive"))
    )
    (net (code "68") (name "Net-(C8-Pad1)") (class "Default")
      (node (ref "C8") (pin "1") (pinfunction "1_1") (pintype "passive"))
      (node (ref "R5") (pin "1") (pinfunction "1_1") (pintype "passive"))
    )
    (net (code "69") (name "Net-(C15-Pad1)") (class "Default")
      (node (ref "C15") (pin "1") (pinfunction "1_1") (pintype "passive"))
      (node (ref "R39") (pin "2") (pinfunction "2_2") (pintype "passive"))
    )
    (net (code "70") (name "Net-(C17-Pad1)") (class "Default")
      (node (ref "C17") (pin "1") (pinfunction "1_1") (pintype "passive"))
      (node (ref "R40") (pin "2") (pinfunction "2_2") (pintype "passive"))
    )
    (net (code "71") (name "Net-(C17-Pad2)") (class "Default")
      (node (ref "C17") (pin "2") (pinfunction "2_2") (pintype "passive"))
      (node (ref "J5") (pin "1") (pinfunction "1_1") (pintype "bidirectional"))
    )
    (net (code "72") (name "Net-(C19-Pad1)") (class "Default")
      (node (ref "C19") (pin "1") (pinfunction "1_1") (pintype "passive"))
      (node (ref "R41") (pin "2") (pinfunction "2_2") (pintype "passive"))
    )
    (net (code "73") (name "Net-(C19-Pad2)") (class "Default")
      (node (ref "C19") (pin "2") (pinfunction "2_2") (pintype "passive"))
      (node (ref "J6") (pin "1") (pinfunction "1_1") (pintype "bidirectional"))
    )
    (net (code "74") (name "Net-(C60-Pad1)") (class "Default")
      (node (ref "C60") (pin "1") (pinfunction "1_1") (pintype "passive"))
      (node (ref "R16") (pin "1") (pinfunction "1_1") (pintype "passive"))
      (node (ref "R17") (pin "2") (pinfunction "2_2") (pintype "passive"))
    )
    (net (code "75") (name "Net-(C61-Pad1)") (class "Default")
      (node (ref "C61") (pin "1") (pinfunction "1_1") (pintype "passive"))
      (node (ref "R18") (pin "2") (pinfunction "2_2") (pintype "passive"))
    )
    (net (code "76") (name "Net-(C83-Pad1)") (class "Default")
      (node (ref "C83") (pin "1") (pinfunction "1_1") (pintype "passive"))
      (node (ref "R29") (pin "1") (pinfunction "1_1") (pintype "passive"))
      (node (ref "R30") (pin "2") (pinfunction "2_2") (pintype "passive"))
    )
    (net (code "77") (name "Net-(C84-Pad1)") (class "Default")
      (node (ref "C84") (pin "1") (pinfunction "1_1") (pintype "passive"))
      (node (ref "R31") (pin "2") (pinfunction "2_2") (pintype "passive"))
    )
    (net (code "78") (name "Net-(C92-Pad2)") (class "Default")
      (node (ref "C92") (pin "2") (pinfunction "2_2") (pintype "passive"))
      (node (ref "J13") (pin "1") (pinfunction "1_1") (pintype "bidirectional"))
    )
    (net (code "79") (name "Net-(D1-PadA)") (class "Default")
      (node (ref "D1") (pin "A") (pinfunction "A_A") (pintype "passive"))
      (node (ref "R21") (pin "1") (pinfunction "1_1") (pintype "passive"))
    )
    (net (code "80") (name "Net-(D2-PadA)") (class "Default")
      (node (ref "D2") (pin "A") (pinfunction "A_A") (pintype "passive"))
      (node (ref "R34") (pin "1") (pinfunction "1_1") (pintype "passive"))
    )
    (net (code "81") (name "Net-(IC1-LDO_PLL1)") (class "Default")
      (node (ref "C3") (pin "2") (pinfunction "2_2") (pintype "passive"))
      (node (ref "IC1") (pin "1") (pinfunction "LDO_PLL1_1") (pintype "bidirectional"))
    )
    (net (code "82") (name "Net-(IC1-LDO_PLL2)") (class "Default")
      (node (ref "C10") (pin "2") (pinfunction "2_2") (pintype "passive"))
      (node (ref "IC1") (pin "12") (pinfunction "LDO_PLL2_12") (pintype "bidirectional"))
    )
    (net (code "83") (name "Net-(IC1-LDO_VCO)") (class "Default")
      (node (ref "C9") (pin "2") (pinfunction "2_2") (pintype "passive"))
      (node (ref "IC1") (pin "14") (pinfunction "LDO_VCO_14") (pintype "bidirectional"))
      (node (ref "R5") (pin "2") (pinfunction "2_2") (pintype "passive"))
    )
    (net (code "84") (name "Net-(IC1-LF1_EXT_CAP)") (class "Default")
      (node (ref "C6") (pin "2") (pinfunction "2_2") (pintype "passive"))
      (node (ref "IC1") (pin "7") (pinfunction "LF1_EXT_CAP_7") (pintype "bidirectional"))
    )
    (net (code "85") (name "Net-(IC1-LF2_EXT_CAP)") (class "Default")
      (node (ref "C8") (pin "2") (pinfunction "2_2") (pintype "passive"))
      (node (ref "IC1") (pin "11") (pinfunction "LF2_EXT_CAP_11") (pintype "bidirectional"))
    )
    (net (code "86") (name "Net-(IC1-OUT6)") (class "Default")
      (node (ref "IC1") (pin "47") (pinfunction "OUT6_47") (pintype "bidirectional"))
      (node (ref "R39") (pin "1") (pinfunction "1_1") (pintype "passive"))
    )
    (net (code "87") (name "Net-(IC1-SCLK{slash}SCL)") (class "Default")
      (node (ref "IC1") (pin "21") (pinfunction "SCLK/SCL_21") (pintype "bidirectional"))
      (node (ref "R6") (pin "2") (pinfunction "2_2") (pintype "passive"))
      (node (ref "R7") (pin "1") (pinfunction "1_1") (pintype "passive"))
    )
    (net (code "88") (name "Net-(IC1-SDIO{slash}SDA)") (class "Default")
      (node (ref "IC1") (pin "22") (pinfunction "SDIO/SDA_22") (pintype "bidirectional"))
      (node (ref "R8") (pin "2") (pinfunction "2_2") (pintype "passive"))
      (node (ref "R9") (pin "1") (pinfunction "1_1") (pintype "passive"))
    )
    (net (code "89") (name "Net-(IC1-~{CS})") (class "Default")
      (node (ref "IC1") (pin "20") (pinfunction "~{CS}_20") (pintype "bidirectional"))
      (node (ref "R10") (pin "2") (pinfunction "2_2") (pintype "passive"))
      (node (ref "R11") (pin "1") (pinfunction "1_1") (pintype "passive"))
    )
    (net (code "90") (name "Net-(IC1-~{OSC_IN})") (class "Default")
      (node (ref "C7") (pin "2") (pinfunction "2_2") (pintype "passive"))
      (node (ref "IC1") (pin "10") (pinfunction "~{OSC_IN}_10") (pintype "bidirectional"))
    )
    (net (code "91") (name "Net-(IC1-~{PLL_OUT})") (class "Default")
      (node (ref "C92") (pin "1") (pinfunction "1_1") (pintype "passive"))
      (node (ref "IC1") (pin "72") (pinfunction "~{PLL_OUT}_72") (pintype "bidirectional"))
    )
    (net (code "92") (name "Net-(IC1-~{REFA})") (class "Default")
      (node (ref "C4") (pin "2") (pinfunction "2_2") (pintype "passive"))
      (node (ref "IC1") (pin "4") (pinfunction "~{REFA}_4") (pintype "bidirectional"))
    )
    (net (code "93") (name "Net-(IC1-~{REFB})") (class "Default")
      (node (ref "C5") (pin "2") (pinfunction "2_2") (pintype "passive"))
      (node (ref "IC1") (pin "6") (pinfunction "~{REFB}_6") (pintype "bidirectional"))
    )
    (net (code "94") (name "Net-(R15-Pad2)") (class "Default")
      (node (ref "R15") (pin "2") (pinfunction "2_2") (pintype "passive"))
      (node (ref "R16") (pin "2") (pinfunction "2_2") (pintype "passive"))
    )
    (net (code "95") (name "Net-(R17-Pad1)") (class "Default")
      (node (ref "R17") (pin "1") (pinfunction "1_1") (pintype "passive"))
      (node (ref "R18") (pin "1") (pinfunction "1_1") (pintype "passive"))
      (node (ref "R19") (pin "2") (pinfunction "2_2") (pintype "passive"))
    )
    (net (code "96") (name "Net-(R19-Pad1)") (class "Default")
      (node (ref "R19") (pin "1") (pinfunction "1_1") (pintype "passive"))
      (node (ref "R20") (pin "2") (pinfunction "2_2") (pintype "passive"))
    )
    (net (code "97") (name "Net-(R28-Pad2)") (class "Default")
      (node (ref "R28") (pin "2") (pinfunction "2_2") (pintype "passive"))
      (node (ref "R29") (pin "2") (pinfunction "2_2") (pintype "passive"))
    )
    (net (code "98") (name "Net-(R30-Pad1)") (class "Default")
      (node (ref "R30") (pin "1") (pinfunction "1_1") (pintype "passive"))
      (node (ref "R31") (pin "1") (pinfunction "1_1") (pintype "passive"))
      (node (ref "R32") (pin "2") (pinfunction "2_2") (pintype "passive"))
    )
    (net (code "99") (name "Net-(R32-Pad1)") (class "Default")
      (node (ref "R32") (pin "1") (pinfunction "1_1") (pintype "passive"))
      (node (ref "R33") (pin "2") (pinfunction "2_2") (pintype "passive"))
    )
    (net (code "100") (name "Net-(U1-CP)") (class "Default")
      (node (ref "C62") (pin "1") (pinfunction "1_1") (pintype "passive"))
      (node (ref "R20") (pin "1") (pinfunction "1_1") (pintype "passive"))
      (node (ref "U1") (pin "47") (pinfunction "CP_47") (pintype "output"))
    )
    (net (code "101") (name "Net-(U1-MUXOUT)") (class "Default")
      (node (ref "J9") (pin "1") (pinfunction "1_1") (pintype "bidirectional"))
      (node (ref "U1") (pin "37") (pinfunction "MUXOUT_37") (pintype "output"))
    )
    (net (code "102") (name "Net-(U1-REFN)") (class "Default")
      (node (ref "C11") (pin "1") (pinfunction "1_1") (pintype "passive"))
      (node (ref "R12") (pin "2") (pinfunction "2_2") (pintype "passive"))
      (node (ref "U1") (pin "43") (pinfunction "REFN_43") (pintype "input"))
    )
    (net (code "103") (name "Net-(U1-REFP)") (class "Default")
      (node (ref "C12") (pin "1") (pinfunction "1_1") (pintype "passive"))
      (node (ref "R12") (pin "1") (pinfunction "1_1") (pintype "passive"))
      (node (ref "U1") (pin "42") (pinfunction "REFP_42") (pintype "input"))
    )
    (net (code "104") (name "Net-(U1-V5_CAL)") (class "Default")
      (node (ref "FB2") (pin "2") (pinfunction "2_2") (pintype "passive"))
      (node (ref "R14") (pin "2") (pinfunction "2_2") (pintype "passive"))
      (node (ref "U1") (pin "8") (pinfunction "V5_CAL_8") (pintype "power_in"))
    )
    (net (code "105") (name "Net-(U1-V5_CP)") (class "Default")
      (node (ref "C59") (pin "2") (pinfunction "2_2") (pintype "passive"))
      (node (ref "FB3") (pin "1") (pinfunction "1_1") (pintype "passive"))
      (node (ref "U1") (pin "46") (pinfunction "V5_CP_46") (pintype "power_in"))
    )
    (net (code "106") (name "Net-(U1-V5_VCO)") (class "Default")
      (node (ref "R14") (pin "1") (pinfunction "1_1") (pintype "passive"))
      (node (ref "U1") (pin "9") (pinfunction "V5_VCO_9") (pintype "power_in"))
    )
    (net (code "107") (name "Net-(U1-VTUNE)") (class "Default")
      (node (ref "R15") (pin "1") (pinfunction "1_1") (pintype "passive"))
      (node (ref "U1") (pin "7") (pinfunction "VTUNE_7") (pintype "input"))
    )
    (net (code "108") (name "Net-(U2-PRIMARY_DOT)") (class "Default")
      (node (ref "U2") (pin "2") (pinfunction "PRIMARY_DOT_2") (pintype "passive"))
      (node (ref "U4") (pin "1") (pinfunction "INPUT_1") (pintype "input"))
    )
    (net (code "109") (name "Net-(U2-SECONDARY)") (class "Default")
      (node (ref "C64") (pin "2") (pinfunction "2_2") (pintype "passive"))
      (node (ref "U2") (pin "9") (pinfunction "SECONDARY_9") (pintype "passive"))
    )
    (net (code "110") (name "Net-(U2-SECONDARY_DOT)") (class "Default")
      (node (ref "C65") (pin "2") (pinfunction "2_2") (pintype "passive"))
      (node (ref "U2") (pin "7") (pinfunction "SECONDARY_DOT_7") (pintype "passive"))
    )
    (net (code "111") (name "Net-(U3-PRIMARY_DOT)") (class "Default")
      (node (ref "U3") (pin "2") (pinfunction "PRIMARY_DOT_2") (pintype "passive"))
      (node (ref "U5") (pin "1") (pinfunction "INPUT_1") (pintype "input"))
    )
    (net (code "112") (name "Net-(U3-SECONDARY)") (class "Default")
      (node (ref "C66") (pin "2") (pinfunction "2_2") (pintype "passive"))
      (node (ref "U3") (pin "9") (pinfunction "SECONDARY_9") (pintype "passive"))
    )
    (net (code "113") (name "Net-(U3-SECONDARY_DOT)") (class "Default")
      (node (ref "C67") (pin "2") (pinfunction "2_2") (pintype "passive"))
      (node (ref "U3") (pin "7") (pinfunction "SECONDARY_DOT_7") (pintype "passive"))
    )
    (net (code "114") (name "Net-(U4-OUTPUT)") (class "Default")
      (node (ref "J10") (pin "1") (pinfunction "1_1") (pintype "bidirectional"))
      (node (ref "U4") (pin "2") (pinfunction "OUTPUT_2") (pintype "output"))
    )
    (net (code "115") (name "Net-(U5-OUTPUT)") (class "Default")
      (node (ref "J1") (pin "1") (pinfunction "1_1") (pintype "bidirectional"))
      (node (ref "U5") (pin "2") (pinfunction "OUTPUT_2") (pintype "output"))
    )
    (net (code "116") (name "Net-(U6-CP)") (class "Default")
      (node (ref "C85") (pin "1") (pinfunction "1_1") (pintype "passive"))
      (node (ref "R33") (pin "1") (pinfunction "1_1") (pintype "passive"))
      (node (ref "U6") (pin "47") (pinfunction "CP_47") (pintype "output"))
    )
    (net (code "117") (name "Net-(U6-MUXOUT)") (class "Default")
      (node (ref "J2") (pin "1") (pinfunction "1_1") (pintype "bidirectional"))
      (node (ref "U6") (pin "37") (pinfunction "MUXOUT_37") (pintype "output"))
    )
    (net (code "118") (name "Net-(U6-REFN)") (class "Default")
      (node (ref "C68") (pin "1") (pinfunction "1_1") (pintype "passive"))
      (node (ref "R1") (pin "2") (pinfunction "2_2") (pintype "passive"))
      (node (ref "U6") (pin "43") (pinfunction "REFN_43") (pintype "input"))
    )
    (net (code "119") (name "Net-(U6-REFP)") (class "Default")
      (node (ref "C69") (pin "1") (pinfunction "1_1") (pintype "passive"))
      (node (ref "R1") (pin "1") (pinfunction "1_1") (pintype "passive"))
      (node (ref "U6") (pin "42") (pinfunction "REFP_42") (pintype "input"))
    )
    (net (code "120") (name "Net-(U6-V5_CAL)") (class "Default")
      (node (ref "FB1") (pin "2") (pinfunction "2_2") (pintype "passive"))
      (node (ref "R27") (pin "2") (pinfunction "2_2") (pintype "passive"))
      (node (ref "U6") (pin "8") (pinfunction "V5_CAL_8") (pintype "power_in"))
    )
    (net (code "121") (name "Net-(U6-V5_CP)") (class "Default")
      (node (ref "C82") (pin "2") (pinfunction "2_2") (pintype "passive"))
      (node (ref "FB4") (pin "1") (pinfunction "1_1") (pintype "passive"))
      (node (ref "U6") (pin "46") (pinfunction "V5_CP_46") (pintype "power_in"))
    )
    (net (code "122") (name "Net-(U6-V5_VCO)") (class "Default")
      (node (ref "R27") (pin "1") (pinfunction "1_1") (pintype "passive"))
      (node (ref "U6") (pin "9") (pinfunction "V5_VCO_9") (pintype "power_in"))
    )
    (net (code "123") (name "Net-(U6-VTUNE)") (class "Default")
      (node (ref "R28") (pin "1") (pinfunction "1_1") (pintype "passive"))
      (node (ref "U6") (pin "7") (pinfunction "VTUNE_7") (pintype "input"))
    )
    (net (code "124") (name "Net-(U7-PRIMARY_DOT)") (class "Default")
      (node (ref "U7") (pin "2") (pinfunction "PRIMARY_DOT_2") (pintype "passive"))
      (node (ref "U8") (pin "1") (pinfunction "INPUT_1") (pintype "input"))
    )
    (net (code "125") (name "Net-(U7-SECONDARY)") (class "Default")
      (node (ref "C87") (pin "2") (pinfunction "2_2") (pintype "passive"))
      (node (ref "U7") (pin "9") (pinfunction "SECONDARY_9") (pintype "passive"))
    )
    (net (code "126") (name "Net-(U7-SECONDARY_DOT)") (class "Default")
      (node (ref "C88") (pin "2") (pinfunction "2_2") (pintype "passive"))
      (node (ref "U7") (pin "7") (pinfunction "SECONDARY_DOT_7") (pintype "passive"))
    )
    (net (code "127") (name "Net-(U8-OUTPUT)") (class "Default")
      (node (ref "J11") (pin "1") (pinfunction "1_1") (pintype "bidirectional"))
      (node (ref "U8") (pin "2") (pinfunction "OUTPUT_2") (pintype "output"))
    )
    (net (code "128") (name "Net-(U9-SECONDARY)") (class "Default")
      (node (ref "C90") (pin "2") (pinfunction "2_2") (pintype "passive"))
      (node (ref "U9") (pin "9") (pinfunction "SECONDARY_9") (pintype "passive"))
    )
    (net (code "129") (name "Net-(U9-SECONDARY_DOT)") (class "Default")
      (node (ref "C91") (pin "2") (pinfunction "2_2") (pintype "passive"))
      (node (ref "U9") (pin "7") (pinfunction "SECONDARY_DOT_7") (pintype "passive"))
    )
    (net (code "130") (name "Net-(U10-INPUT)") (class "Default")
      (node (ref "U10") (pin "1") (pinfunction "INPUT_1") (pintype "input"))
      (node (ref "U9") (pin "2") (pinfunction "PRIMARY_DOT_2") (pintype "passive"))
    )
    (net (code "131") (name "Net-(U10-OUTPUT)") (class "Default")
      (node (ref "J12") (pin "1") (pinfunction "1_1") (pintype "bidirectional"))
      (node (ref "U10") (pin "2") (pinfunction "OUTPUT_2") (pintype "output"))
    )
    (net (code "132") (name "Net-(X4-VOLTAGE_CONTROL)") (class "Default")
      (node (ref "R2") (pin "1") (pinfunction "1_1") (pintype "passive"))
      (node (ref "R3") (pin "2") (pinfunction "2_2") (pintype "passive"))
      (node (ref "X4") (pin "1") (pinfunction "VOLTAGE_CONTROL_1") (pintype "passive"))
    )
    (net (code "133") (name "Net-(X6-VOLT_CONTROL)") (class "Default")
      (node (ref "C2") (pin "1") (pinfunction "1_1") (pintype "passive"))
      (node (ref "R4") (pin "1") (pinfunction "1_1") (pintype "passive"))
      (node (ref "X6") (pin "1") (pinfunction "VOLT_CONTROL_1") (pintype "passive"))
    )
    (net (code "134") (name "Net-(X10A-S)") (class "Default")
      (node (ref "C21") (pin "1") (pinfunction "1_1") (pintype "passive"))
      (node (ref "L9") (pin "2") (pinfunction "2_2") (pintype "passive"))
      (node (ref "X10") (pin "1") (pinfunction "S_1") (pintype "passive"))
    )
    (net (code "135") (name "Net-(X11A-S)") (class "Default")
      (node (ref "C25") (pin "1") (pinfunction "1_1") (pintype "passive"))
      (node (ref "L10") (pin "2") (pinfunction "2_2") (pintype "passive"))
      (node (ref "X11") (pin "1") (pinfunction "S_1") (pintype "passive"))
    )
    (net (code "136") (name "Net-(X12A-S)") (class "Default")
      (node (ref "C29") (pin "1") (pinfunction "1_1") (pintype "passive"))
      (node (ref "L11") (pin "2") (pinfunction "2_2") (pintype "passive"))
      (node (ref "X12") (pin "1") (pinfunction "S_1") (pintype "passive"))
    )
    (net (code "137") (name "Net-(X13A-S)") (class "Default")
      (node (ref "C33") (pin "1") (pinfunction "1_1") (pintype "passive"))
      (node (ref "L12") (pin "2") (pinfunction "2_2") (pintype "passive"))
      (node (ref "X13") (pin "1") (pinfunction "S_1") (pintype "passive"))
    )
    (net (code "138") (name "Net-(X14A-S)") (class "Default")
      (node (ref "C46") (pin "1") (pinfunction "1_1") (pintype "passive"))
      (node (ref "L13") (pin "2") (pinfunction "2_2") (pintype "passive"))
      (node (ref "X14") (pin "1") (pinfunction "S_1") (pintype "passive"))
    )
    (net (code "139") (name "unconnected-(IC1-OUT12-Pad29)") (class "Default")
      (node (ref "IC1") (pin "29") (pinfunction "OUT12_29") (pintype "bidirectional"))
    )
    (net (code "140") (name "unconnected-(IC1-OUT13-Pad26)") (class "Default")
      (node (ref "IC1") (pin "26") (pinfunction "OUT13_26") (pintype "bidirectional"))
    )
    (net (code "141") (name "unconnected-(IC1-REF_TEST-Pad24)") (class "Default")
      (node (ref "IC1") (pin "24") (pinfunction "REF_TEST_24") (pintype "bidirectional"))
    )
    (net (code "142") (name "unconnected-(IC1-ZD_IN-Pad70)") (class "Default")
      (node (ref "IC1") (pin "70") (pinfunction "ZD_IN_70") (pintype "bidirectional"))
    )
    (net (code "143") (name "unconnected-(IC1-~{OUT6}-Pad46)") (class "Default")
      (node (ref "IC1") (pin "46") (pinfunction "~{OUT6}_46") (pintype "bidirectional"))
    )
    (net (code "144") (name "unconnected-(IC1-~{OUT7}-Pad43)") (class "Default")
      (node (ref "IC1") (pin "43") (pinfunction "~{OUT7}_43") (pintype "bidirectional"))
    )
    (net (code "145") (name "unconnected-(IC1-~{OUT10}-Pad34)") (class "Default")
      (node (ref "IC1") (pin "34") (pinfunction "~{OUT10}_34") (pintype "bidirectional"))
    )
    (net (code "146") (name "unconnected-(IC1-~{OUT11}-Pad31)") (class "Default")
      (node (ref "IC1") (pin "31") (pinfunction "~{OUT11}_31") (pintype "bidirectional"))
    )
    (net (code "147") (name "unconnected-(IC1-~{OUT12}-Pad28)") (class "Default")
      (node (ref "IC1") (pin "28") (pinfunction "~{OUT12}_28") (pintype "bidirectional"))
    )
    (net (code "148") (name "unconnected-(IC1-~{OUT13}-Pad25)") (class "Default")
      (node (ref "IC1") (pin "25") (pinfunction "~{OUT13}_25") (pintype "bidirectional"))
    )
    (net (code "149") (name "unconnected-(IC1-~{ZD_IN}-Pad71)") (class "Default")
      (node (ref "IC1") (pin "71") (pinfunction "~{ZD_IN}_71") (pintype "bidirectional"))
    )
    (net (code "150") (name "unconnected-(U1-VG_BIAS-Pad6)") (class "Default")
      (node (ref "U1") (pin "6") (pinfunction "VG_BIAS_6") (pintype "no_connect"))
    )
    (net (code "151") (name "unconnected-(U2-NO_CONNECTION-Pad4)") (class "Default")
      (node (ref "U2") (pin "4") (pinfunction "NO_CONNECTION_4") (pintype "no_connect"))
    )
    (net (code "152") (name "unconnected-(U2-NO_CONNECTION_2-Pad5)") (class "Default")
      (node (ref "U2") (pin "5") (pinfunction "NO_CONNECTION_2_5") (pintype "no_connect"))
    )
    (net (code "153") (name "unconnected-(U2-NO_CONNECTION_3-Pad8)") (class "Default")
      (node (ref "U2") (pin "8") (pinfunction "NO_CONNECTION_3_8") (pintype "no_connect"))
    )
    (net (code "154") (name "unconnected-(U2-NO_CONNECTION_4-Pad11)") (class "Default")
      (node (ref "U2") (pin "11") (pinfunction "NO_CONNECTION_4_11") (pintype "no_connect"))
    )
    (net (code "155") (name "unconnected-(U2-NO_CONNECTION_5-Pad12)") (class "Default")
      (node (ref "U2") (pin "12") (pinfunction "NO_CONNECTION_5_12") (pintype "no_connect"))
    )
    (net (code "156") (name "unconnected-(U3-NO_CONNECTION-Pad4)") (class "Default")
      (node (ref "U3") (pin "4") (pinfunction "NO_CONNECTION_4") (pintype "no_connect"))
    )
    (net (code "157") (name "unconnected-(U3-NO_CONNECTION_2-Pad5)") (class "Default")
      (node (ref "U3") (pin "5") (pinfunction "NO_CONNECTION_2_5") (pintype "no_connect"))
    )
    (net (code "158") (name "unconnected-(U3-NO_CONNECTION_3-Pad8)") (class "Default")
      (node (ref "U3") (pin "8") (pinfunction "NO_CONNECTION_3_8") (pintype "no_connect"))
    )
    (net (code "159") (name "unconnected-(U3-NO_CONNECTION_4-Pad11)") (class "Default")
      (node (ref "U3") (pin "11") (pinfunction "NO_CONNECTION_4_11") (pintype "no_connect"))
    )
    (net (code "160") (name "unconnected-(U3-NO_CONNECTION_5-Pad12)") (class "Default")
      (node (ref "U3") (pin "12") (pinfunction "NO_CONNECTION_5_12") (pintype "no_connect"))
    )
    (net (code "161") (name "unconnected-(U6-VG_BIAS-Pad6)") (class "Default")
      (node (ref "U6") (pin "6") (pinfunction "VG_BIAS_6") (pintype "no_connect"))
    )
    (net (code "162") (name "unconnected-(U7-NO_CONNECTION-Pad4)") (class "Default")
      (node (ref "U7") (pin "4") (pinfunction "NO_CONNECTION_4") (pintype "no_connect"))
    )
    (net (code "163") (name "unconnected-(U7-NO_CONNECTION_2-Pad5)") (class "Default")
      (node (ref "U7") (pin "5") (pinfunction "NO_CONNECTION_2_5") (pintype "no_connect"))
    )
    (net (code "164") (name "unconnected-(U7-NO_CONNECTION_3-Pad8)") (class "Default")
      (node (ref "U7") (pin "8") (pinfunction "NO_CONNECTION_3_8") (pintype "no_connect"))
    )
    (net (code "165") (name "unconnected-(U7-NO_CONNECTION_4-Pad11)") (class "Default")
      (node (ref "U7") (pin "11") (pinfunction "NO_CONNECTION_4_11") (pintype "no_connect"))
    )
    (net (code "166") (name "unconnected-(U7-NO_CONNECTION_5-Pad12)") (class "Default")
      (node (ref "U7") (pin "12") (pinfunction "NO_CONNECTION_5_12") (pintype "no_connect"))
    )
    (net (code "167") (name "unconnected-(U9-NO_CONNECTION-Pad4)") (class "Default")
      (node (ref "U9") (pin "4") (pinfunction "NO_CONNECTION_4") (pintype "no_connect"))
    )
    (net (code "168") (name "unconnected-(U9-NO_CONNECTION_2-Pad5)") (class "Default")
      (node (ref "U9") (pin "5") (pinfunction "NO_CONNECTION_2_5") (pintype "no_connect"))
    )
    (net (code "169") (name "unconnected-(U9-NO_CONNECTION_3-Pad8)") (class "Default")
      (node (ref "U9") (pin "8") (pinfunction "NO_CONNECTION_3_8") (pintype "no_connect"))
    )
    (net (code "170") (name "unconnected-(U9-NO_CONNECTION_4-Pad11)") (class "Default")
      (node (ref "U9") (pin "11") (pinfunction "NO_CONNECTION_4_11") (pintype "no_connect"))
    )
    (net (code "171") (name "unconnected-(U9-NO_CONNECTION_5-Pad12)") (class "Default")
      (node (ref "U9") (pin "12") (pinfunction "NO_CONNECTION_5_12") (pintype "no_connect"))
    )
    (net (code "172") (name "unconnected-(X4-V_REF-Pad2)") (class "Default")
      (node (ref "X4") (pin "2") (pinfunction "V_REF_2") (pintype "passive"))
    )
    (net (code "173") (name "unconnected-(X5-VOLT_CONTROL-Pad1)") (class "Default")
      (node (ref "X5") (pin "1") (pinfunction "VOLT_CONTROL_1") (pintype "passive"))
    )
  )
)
